# pixelpal.net
KiCad netlist of a schematic drawn in EasyEDA
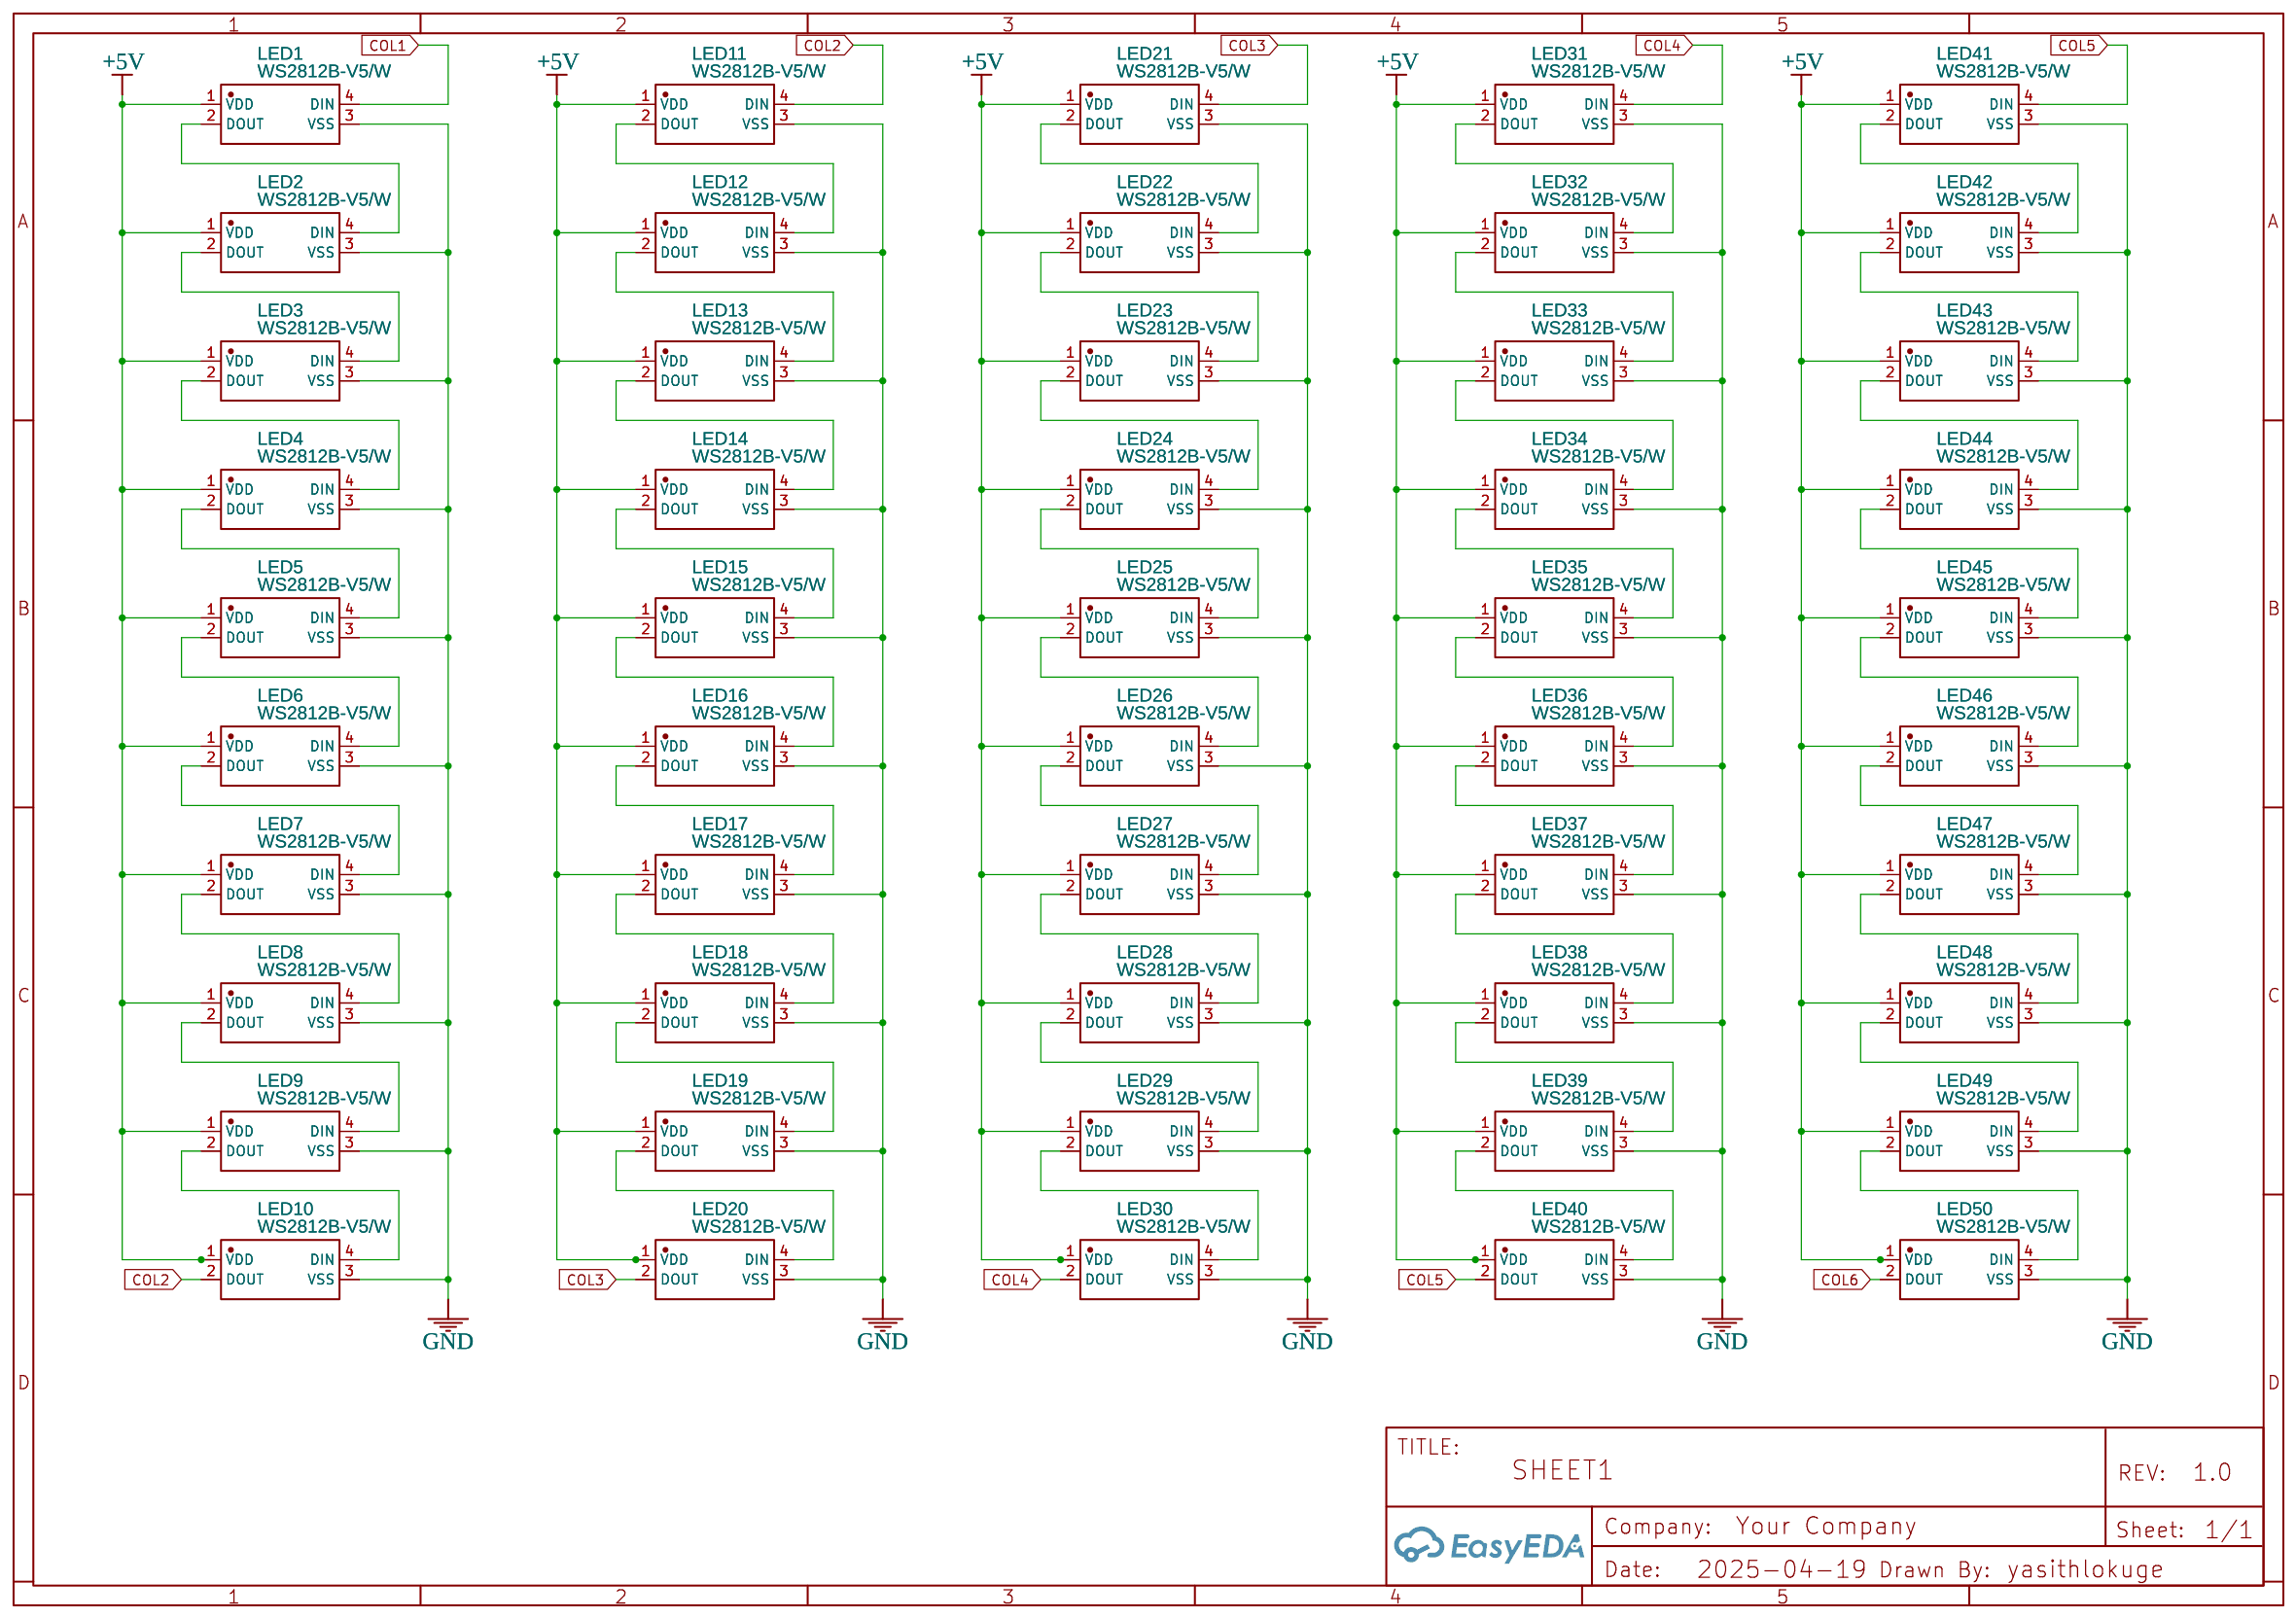
[diagram p0: SHEET1]
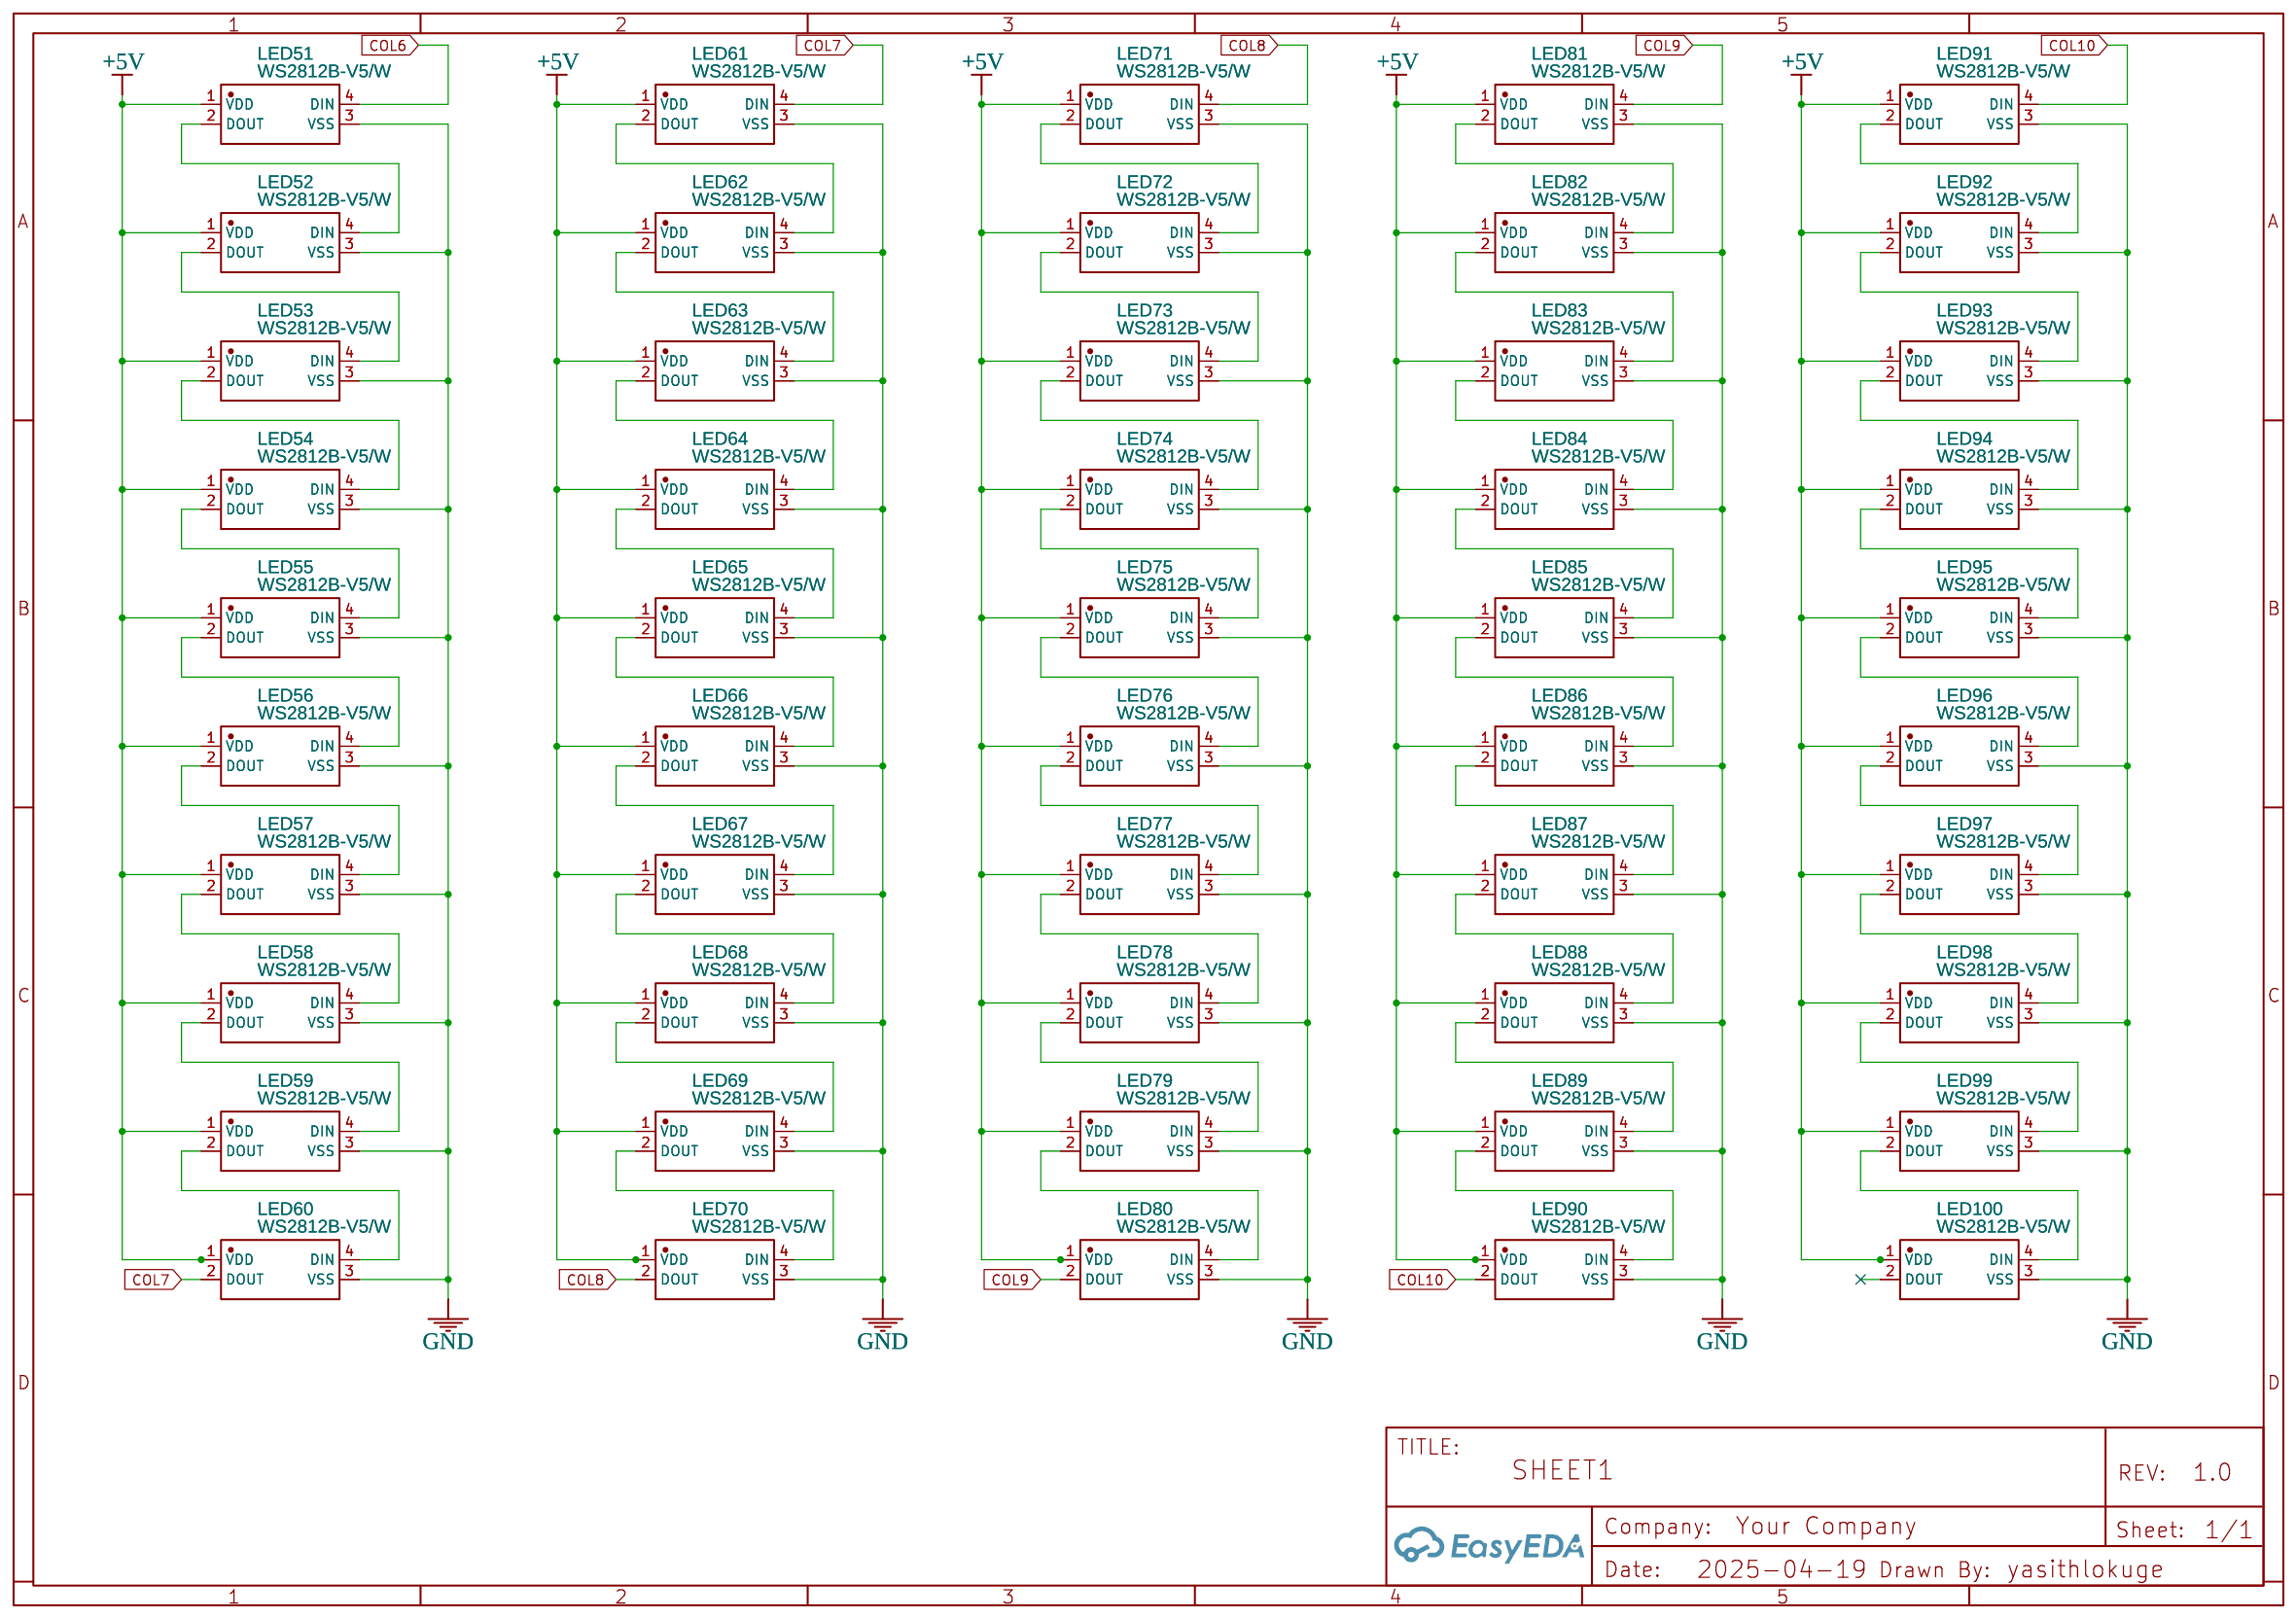
[diagram p1: SHEET2]
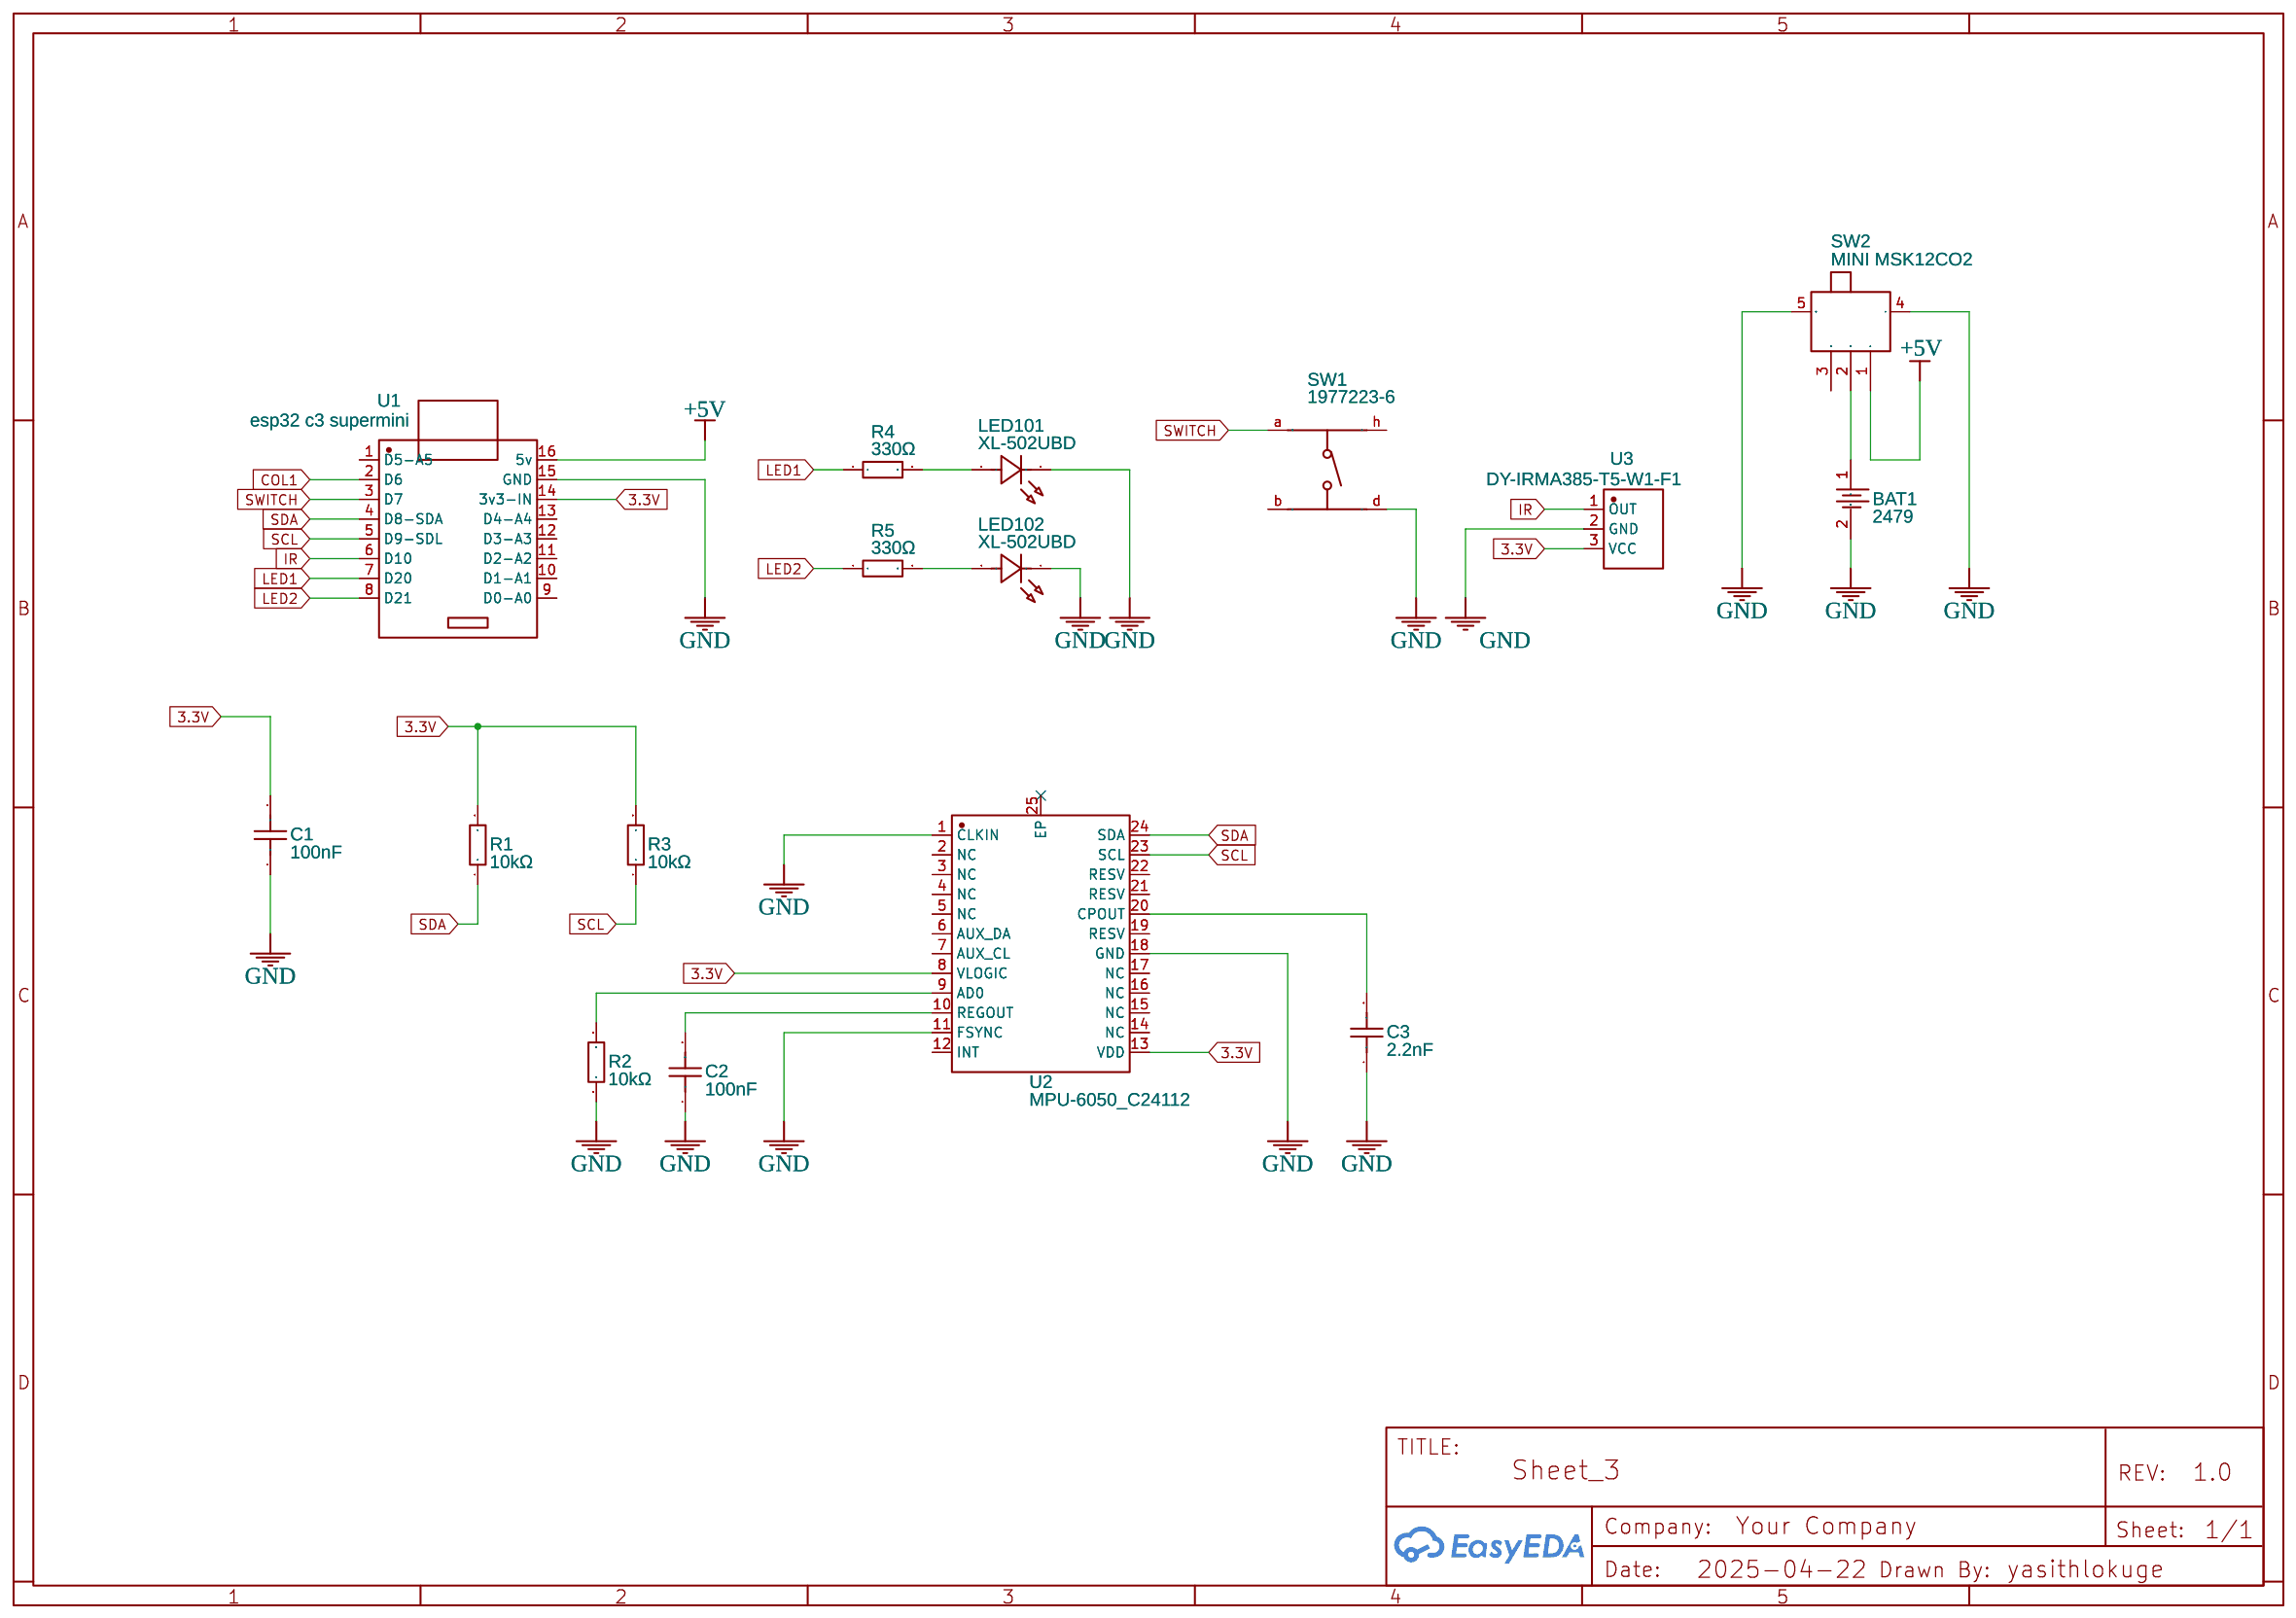
[diagram p2: SHEET3]

(export (version "E")
  (design (tool "Eeschema 10.0.6"))
  (components
    (comp (ref "LED1")
      (value "WS2812B-V5/W")
      (fields (field (name "Manufacturer") "worldsemi"))
      (libsource (lib "") (part "WS2812B-V5/W"))
    )
    (comp (ref "LED2")
      (value "WS2812B-V5/W")
      (fields (field (name "Manufacturer") "worldsemi"))
      (libsource (lib "") (part "WS2812B-V5/W"))
    )
    (comp (ref "LED3")
      (value "WS2812B-V5/W")
      (fields (field (name "Manufacturer") "worldsemi"))
      (libsource (lib "") (part "WS2812B-V5/W"))
    )
    (comp (ref "LED4")
      (value "WS2812B-V5/W")
      (fields (field (name "Manufacturer") "worldsemi"))
      (libsource (lib "") (part "WS2812B-V5/W"))
    )
    (comp (ref "LED5")
      (value "WS2812B-V5/W")
      (fields (field (name "Manufacturer") "worldsemi"))
      (libsource (lib "") (part "WS2812B-V5/W"))
    )
    (comp (ref "LED6")
      (value "WS2812B-V5/W")
      (fields (field (name "Manufacturer") "worldsemi"))
      (libsource (lib "") (part "WS2812B-V5/W"))
    )
    (comp (ref "LED7")
      (value "WS2812B-V5/W")
      (fields (field (name "Manufacturer") "worldsemi"))
      (libsource (lib "") (part "WS2812B-V5/W"))
    )
    (comp (ref "LED8")
      (value "WS2812B-V5/W")
      (fields (field (name "Manufacturer") "worldsemi"))
      (libsource (lib "") (part "WS2812B-V5/W"))
    )
    (comp (ref "LED9")
      (value "WS2812B-V5/W")
      (fields (field (name "Manufacturer") "worldsemi"))
      (libsource (lib "") (part "WS2812B-V5/W"))
    )
    (comp (ref "LED10")
      (value "WS2812B-V5/W")
      (fields (field (name "Manufacturer") "worldsemi"))
      (libsource (lib "") (part "WS2812B-V5/W"))
    )
    (comp (ref "LED11")
      (value "WS2812B-V5/W")
      (fields (field (name "Manufacturer") "worldsemi"))
      (libsource (lib "") (part "WS2812B-V5/W"))
    )
    (comp (ref "LED12")
      (value "WS2812B-V5/W")
      (fields (field (name "Manufacturer") "worldsemi"))
      (libsource (lib "") (part "WS2812B-V5/W"))
    )
    (comp (ref "LED13")
      (value "WS2812B-V5/W")
      (fields (field (name "Manufacturer") "worldsemi"))
      (libsource (lib "") (part "WS2812B-V5/W"))
    )
    (comp (ref "LED14")
      (value "WS2812B-V5/W")
      (fields (field (name "Manufacturer") "worldsemi"))
      (libsource (lib "") (part "WS2812B-V5/W"))
    )
    (comp (ref "LED15")
      (value "WS2812B-V5/W")
      (fields (field (name "Manufacturer") "worldsemi"))
      (libsource (lib "") (part "WS2812B-V5/W"))
    )
    (comp (ref "LED16")
      (value "WS2812B-V5/W")
      (fields (field (name "Manufacturer") "worldsemi"))
      (libsource (lib "") (part "WS2812B-V5/W"))
    )
    (comp (ref "LED17")
      (value "WS2812B-V5/W")
      (fields (field (name "Manufacturer") "worldsemi"))
      (libsource (lib "") (part "WS2812B-V5/W"))
    )
    (comp (ref "LED18")
      (value "WS2812B-V5/W")
      (fields (field (name "Manufacturer") "worldsemi"))
      (libsource (lib "") (part "WS2812B-V5/W"))
    )
    (comp (ref "LED19")
      (value "WS2812B-V5/W")
      (fields (field (name "Manufacturer") "worldsemi"))
      (libsource (lib "") (part "WS2812B-V5/W"))
    )
    (comp (ref "LED20")
      (value "WS2812B-V5/W")
      (fields (field (name "Manufacturer") "worldsemi"))
      (libsource (lib "") (part "WS2812B-V5/W"))
    )
    (comp (ref "LED21")
      (value "WS2812B-V5/W")
      (fields (field (name "Manufacturer") "worldsemi"))
      (libsource (lib "") (part "WS2812B-V5/W"))
    )
    (comp (ref "LED22")
      (value "WS2812B-V5/W")
      (fields (field (name "Manufacturer") "worldsemi"))
      (libsource (lib "") (part "WS2812B-V5/W"))
    )
    (comp (ref "LED23")
      (value "WS2812B-V5/W")
      (fields (field (name "Manufacturer") "worldsemi"))
      (libsource (lib "") (part "WS2812B-V5/W"))
    )
    (comp (ref "LED24")
      (value "WS2812B-V5/W")
      (fields (field (name "Manufacturer") "worldsemi"))
      (libsource (lib "") (part "WS2812B-V5/W"))
    )
    (comp (ref "LED25")
      (value "WS2812B-V5/W")
      (fields (field (name "Manufacturer") "worldsemi"))
      (libsource (lib "") (part "WS2812B-V5/W"))
    )
    (comp (ref "LED26")
      (value "WS2812B-V5/W")
      (fields (field (name "Manufacturer") "worldsemi"))
      (libsource (lib "") (part "WS2812B-V5/W"))
    )
    (comp (ref "LED27")
      (value "WS2812B-V5/W")
      (fields (field (name "Manufacturer") "worldsemi"))
      (libsource (lib "") (part "WS2812B-V5/W"))
    )
    (comp (ref "LED28")
      (value "WS2812B-V5/W")
      (fields (field (name "Manufacturer") "worldsemi"))
      (libsource (lib "") (part "WS2812B-V5/W"))
    )
    (comp (ref "LED29")
      (value "WS2812B-V5/W")
      (fields (field (name "Manufacturer") "worldsemi"))
      (libsource (lib "") (part "WS2812B-V5/W"))
    )
    (comp (ref "LED30")
      (value "WS2812B-V5/W")
      (fields (field (name "Manufacturer") "worldsemi"))
      (libsource (lib "") (part "WS2812B-V5/W"))
    )
    (comp (ref "LED31")
      (value "WS2812B-V5/W")
      (fields (field (name "Manufacturer") "worldsemi"))
      (libsource (lib "") (part "WS2812B-V5/W"))
    )
    (comp (ref "LED32")
      (value "WS2812B-V5/W")
      (fields (field (name "Manufacturer") "worldsemi"))
      (libsource (lib "") (part "WS2812B-V5/W"))
    )
    (comp (ref "LED33")
      (value "WS2812B-V5/W")
      (fields (field (name "Manufacturer") "worldsemi"))
      (libsource (lib "") (part "WS2812B-V5/W"))
    )
    (comp (ref "LED34")
      (value "WS2812B-V5/W")
      (fields (field (name "Manufacturer") "worldsemi"))
      (libsource (lib "") (part "WS2812B-V5/W"))
    )
    (comp (ref "LED35")
      (value "WS2812B-V5/W")
      (fields (field (name "Manufacturer") "worldsemi"))
      (libsource (lib "") (part "WS2812B-V5/W"))
    )
    (comp (ref "LED36")
      (value "WS2812B-V5/W")
      (fields (field (name "Manufacturer") "worldsemi"))
      (libsource (lib "") (part "WS2812B-V5/W"))
    )
    (comp (ref "LED37")
      (value "WS2812B-V5/W")
      (fields (field (name "Manufacturer") "worldsemi"))
      (libsource (lib "") (part "WS2812B-V5/W"))
    )
    (comp (ref "LED38")
      (value "WS2812B-V5/W")
      (fields (field (name "Manufacturer") "worldsemi"))
      (libsource (lib "") (part "WS2812B-V5/W"))
    )
    (comp (ref "LED39")
      (value "WS2812B-V5/W")
      (fields (field (name "Manufacturer") "worldsemi"))
      (libsource (lib "") (part "WS2812B-V5/W"))
    )
    (comp (ref "LED40")
      (value "WS2812B-V5/W")
      (fields (field (name "Manufacturer") "worldsemi"))
      (libsource (lib "") (part "WS2812B-V5/W"))
    )
    (comp (ref "LED41")
      (value "WS2812B-V5/W")
      (fields (field (name "Manufacturer") "worldsemi"))
      (libsource (lib "") (part "WS2812B-V5/W"))
    )
    (comp (ref "LED42")
      (value "WS2812B-V5/W")
      (fields (field (name "Manufacturer") "worldsemi"))
      (libsource (lib "") (part "WS2812B-V5/W"))
    )
    (comp (ref "LED43")
      (value "WS2812B-V5/W")
      (fields (field (name "Manufacturer") "worldsemi"))
      (libsource (lib "") (part "WS2812B-V5/W"))
    )
    (comp (ref "LED44")
      (value "WS2812B-V5/W")
      (fields (field (name "Manufacturer") "worldsemi"))
      (libsource (lib "") (part "WS2812B-V5/W"))
    )
    (comp (ref "LED45")
      (value "WS2812B-V5/W")
      (fields (field (name "Manufacturer") "worldsemi"))
      (libsource (lib "") (part "WS2812B-V5/W"))
    )
    (comp (ref "LED46")
      (value "WS2812B-V5/W")
      (fields (field (name "Manufacturer") "worldsemi"))
      (libsource (lib "") (part "WS2812B-V5/W"))
    )
    (comp (ref "LED47")
      (value "WS2812B-V5/W")
      (fields (field (name "Manufacturer") "worldsemi"))
      (libsource (lib "") (part "WS2812B-V5/W"))
    )
    (comp (ref "LED48")
      (value "WS2812B-V5/W")
      (fields (field (name "Manufacturer") "worldsemi"))
      (libsource (lib "") (part "WS2812B-V5/W"))
    )
    (comp (ref "LED49")
      (value "WS2812B-V5/W")
      (fields (field (name "Manufacturer") "worldsemi"))
      (libsource (lib "") (part "WS2812B-V5/W"))
    )
    (comp (ref "LED50")
      (value "WS2812B-V5/W")
      (fields (field (name "Manufacturer") "worldsemi"))
      (libsource (lib "") (part "WS2812B-V5/W"))
    )
    (comp (ref "LED51")
      (value "WS2812B-V5/W")
      (fields (field (name "Manufacturer") "worldsemi"))
      (libsource (lib "") (part "WS2812B-V5/W"))
    )
    (comp (ref "LED52")
      (value "WS2812B-V5/W")
      (fields (field (name "Manufacturer") "worldsemi"))
      (libsource (lib "") (part "WS2812B-V5/W"))
    )
    (comp (ref "LED53")
      (value "WS2812B-V5/W")
      (fields (field (name "Manufacturer") "worldsemi"))
      (libsource (lib "") (part "WS2812B-V5/W"))
    )
    (comp (ref "LED54")
      (value "WS2812B-V5/W")
      (fields (field (name "Manufacturer") "worldsemi"))
      (libsource (lib "") (part "WS2812B-V5/W"))
    )
    (comp (ref "LED55")
      (value "WS2812B-V5/W")
      (fields (field (name "Manufacturer") "worldsemi"))
      (libsource (lib "") (part "WS2812B-V5/W"))
    )
    (comp (ref "LED56")
      (value "WS2812B-V5/W")
      (fields (field (name "Manufacturer") "worldsemi"))
      (libsource (lib "") (part "WS2812B-V5/W"))
    )
    (comp (ref "LED57")
      (value "WS2812B-V5/W")
      (fields (field (name "Manufacturer") "worldsemi"))
      (libsource (lib "") (part "WS2812B-V5/W"))
    )
    (comp (ref "LED58")
      (value "WS2812B-V5/W")
      (fields (field (name "Manufacturer") "worldsemi"))
      (libsource (lib "") (part "WS2812B-V5/W"))
    )
    (comp (ref "LED59")
      (value "WS2812B-V5/W")
      (fields (field (name "Manufacturer") "worldsemi"))
      (libsource (lib "") (part "WS2812B-V5/W"))
    )
    (comp (ref "LED60")
      (value "WS2812B-V5/W")
      (fields (field (name "Manufacturer") "worldsemi"))
      (libsource (lib "") (part "WS2812B-V5/W"))
    )
    (comp (ref "LED61")
      (value "WS2812B-V5/W")
      (fields (field (name "Manufacturer") "worldsemi"))
      (libsource (lib "") (part "WS2812B-V5/W"))
    )
    (comp (ref "LED62")
      (value "WS2812B-V5/W")
      (fields (field (name "Manufacturer") "worldsemi"))
      (libsource (lib "") (part "WS2812B-V5/W"))
    )
    (comp (ref "LED63")
      (value "WS2812B-V5/W")
      (fields (field (name "Manufacturer") "worldsemi"))
      (libsource (lib "") (part "WS2812B-V5/W"))
    )
    (comp (ref "LED64")
      (value "WS2812B-V5/W")
      (fields (field (name "Manufacturer") "worldsemi"))
      (libsource (lib "") (part "WS2812B-V5/W"))
    )
    (comp (ref "LED65")
      (value "WS2812B-V5/W")
      (fields (field (name "Manufacturer") "worldsemi"))
      (libsource (lib "") (part "WS2812B-V5/W"))
    )
    (comp (ref "LED66")
      (value "WS2812B-V5/W")
      (fields (field (name "Manufacturer") "worldsemi"))
      (libsource (lib "") (part "WS2812B-V5/W"))
    )
    (comp (ref "LED67")
      (value "WS2812B-V5/W")
      (fields (field (name "Manufacturer") "worldsemi"))
      (libsource (lib "") (part "WS2812B-V5/W"))
    )
    (comp (ref "LED68")
      (value "WS2812B-V5/W")
      (fields (field (name "Manufacturer") "worldsemi"))
      (libsource (lib "") (part "WS2812B-V5/W"))
    )
    (comp (ref "LED69")
      (value "WS2812B-V5/W")
      (fields (field (name "Manufacturer") "worldsemi"))
      (libsource (lib "") (part "WS2812B-V5/W"))
    )
    (comp (ref "LED70")
      (value "WS2812B-V5/W")
      (fields (field (name "Manufacturer") "worldsemi"))
      (libsource (lib "") (part "WS2812B-V5/W"))
    )
    (comp (ref "LED71")
      (value "WS2812B-V5/W")
      (fields (field (name "Manufacturer") "worldsemi"))
      (libsource (lib "") (part "WS2812B-V5/W"))
    )
    (comp (ref "LED72")
      (value "WS2812B-V5/W")
      (fields (field (name "Manufacturer") "worldsemi"))
      (libsource (lib "") (part "WS2812B-V5/W"))
    )
    (comp (ref "LED73")
      (value "WS2812B-V5/W")
      (fields (field (name "Manufacturer") "worldsemi"))
      (libsource (lib "") (part "WS2812B-V5/W"))
    )
    (comp (ref "LED74")
      (value "WS2812B-V5/W")
      (fields (field (name "Manufacturer") "worldsemi"))
      (libsource (lib "") (part "WS2812B-V5/W"))
    )
    (comp (ref "LED75")
      (value "WS2812B-V5/W")
      (fields (field (name "Manufacturer") "worldsemi"))
      (libsource (lib "") (part "WS2812B-V5/W"))
    )
    (comp (ref "LED76")
      (value "WS2812B-V5/W")
      (fields (field (name "Manufacturer") "worldsemi"))
      (libsource (lib "") (part "WS2812B-V5/W"))
    )
    (comp (ref "LED77")
      (value "WS2812B-V5/W")
      (fields (field (name "Manufacturer") "worldsemi"))
      (libsource (lib "") (part "WS2812B-V5/W"))
    )
    (comp (ref "LED78")
      (value "WS2812B-V5/W")
      (fields (field (name "Manufacturer") "worldsemi"))
      (libsource (lib "") (part "WS2812B-V5/W"))
    )
    (comp (ref "LED79")
      (value "WS2812B-V5/W")
      (fields (field (name "Manufacturer") "worldsemi"))
      (libsource (lib "") (part "WS2812B-V5/W"))
    )
    (comp (ref "LED80")
      (value "WS2812B-V5/W")
      (fields (field (name "Manufacturer") "worldsemi"))
      (libsource (lib "") (part "WS2812B-V5/W"))
    )
    (comp (ref "LED81")
      (value "WS2812B-V5/W")
      (fields (field (name "Manufacturer") "worldsemi"))
      (libsource (lib "") (part "WS2812B-V5/W"))
    )
    (comp (ref "LED82")
      (value "WS2812B-V5/W")
      (fields (field (name "Manufacturer") "worldsemi"))
      (libsource (lib "") (part "WS2812B-V5/W"))
    )
    (comp (ref "LED83")
      (value "WS2812B-V5/W")
      (fields (field (name "Manufacturer") "worldsemi"))
      (libsource (lib "") (part "WS2812B-V5/W"))
    )
    (comp (ref "LED84")
      (value "WS2812B-V5/W")
      (fields (field (name "Manufacturer") "worldsemi"))
      (libsource (lib "") (part "WS2812B-V5/W"))
    )
    (comp (ref "LED85")
      (value "WS2812B-V5/W")
      (fields (field (name "Manufacturer") "worldsemi"))
      (libsource (lib "") (part "WS2812B-V5/W"))
    )
    (comp (ref "LED86")
      (value "WS2812B-V5/W")
      (fields (field (name "Manufacturer") "worldsemi"))
      (libsource (lib "") (part "WS2812B-V5/W"))
    )
    (comp (ref "LED87")
      (value "WS2812B-V5/W")
      (fields (field (name "Manufacturer") "worldsemi"))
      (libsource (lib "") (part "WS2812B-V5/W"))
    )
    (comp (ref "LED88")
      (value "WS2812B-V5/W")
      (fields (field (name "Manufacturer") "worldsemi"))
      (libsource (lib "") (part "WS2812B-V5/W"))
    )
    (comp (ref "LED89")
      (value "WS2812B-V5/W")
      (fields (field (name "Manufacturer") "worldsemi"))
      (libsource (lib "") (part "WS2812B-V5/W"))
    )
    (comp (ref "LED90")
      (value "WS2812B-V5/W")
      (fields (field (name "Manufacturer") "worldsemi"))
      (libsource (lib "") (part "WS2812B-V5/W"))
    )
    (comp (ref "LED91")
      (value "WS2812B-V5/W")
      (fields (field (name "Manufacturer") "worldsemi"))
      (libsource (lib "") (part "WS2812B-V5/W"))
    )
    (comp (ref "LED92")
      (value "WS2812B-V5/W")
      (fields (field (name "Manufacturer") "worldsemi"))
      (libsource (lib "") (part "WS2812B-V5/W"))
    )
    (comp (ref "LED93")
      (value "WS2812B-V5/W")
      (fields (field (name "Manufacturer") "worldsemi"))
      (libsource (lib "") (part "WS2812B-V5/W"))
    )
    (comp (ref "LED94")
      (value "WS2812B-V5/W")
      (fields (field (name "Manufacturer") "worldsemi"))
      (libsource (lib "") (part "WS2812B-V5/W"))
    )
    (comp (ref "LED95")
      (value "WS2812B-V5/W")
      (fields (field (name "Manufacturer") "worldsemi"))
      (libsource (lib "") (part "WS2812B-V5/W"))
    )
    (comp (ref "LED96")
      (value "WS2812B-V5/W")
      (fields (field (name "Manufacturer") "worldsemi"))
      (libsource (lib "") (part "WS2812B-V5/W"))
    )
    (comp (ref "LED97")
      (value "WS2812B-V5/W")
      (fields (field (name "Manufacturer") "worldsemi"))
      (libsource (lib "") (part "WS2812B-V5/W"))
    )
    (comp (ref "LED98")
      (value "WS2812B-V5/W")
      (fields (field (name "Manufacturer") "worldsemi"))
      (libsource (lib "") (part "WS2812B-V5/W"))
    )
    (comp (ref "LED99")
      (value "WS2812B-V5/W")
      (fields (field (name "Manufacturer") "worldsemi"))
      (libsource (lib "") (part "WS2812B-V5/W"))
    )
    (comp (ref "LED100")
      (value "WS2812B-V5/W")
      (fields (field (name "Manufacturer") "worldsemi"))
      (libsource (lib "") (part "WS2812B-V5/W"))
    )
    (comp (ref "BAT1")
      (value "2479")
      (fields (field (name "Manufacturer") "Keystone"))
      (libsource (lib "") (part "2479"))
    )
    (comp (ref "C1")
      (value "100nF")
      (fields
        (field (name "Manufacturer Part") "CL05B104KP5VPNC")
        (field (name "Manufacturer") "SAMSUNG(三星)")
      )
      (libsource (lib "") (part "CL05B104KP5VPNC"))
    )
    (comp (ref "C2")
      (value "100nF")
      (fields
        (field (name "Manufacturer Part") "CL05B104KP5VPNC")
        (field (name "Manufacturer") "SAMSUNG(三星)")
      )
      (libsource (lib "") (part "CL05B104KP5VPNC"))
    )
    (comp (ref "C3")
      (value "2.2nF")
      (fields
        (field (name "Manufacturer Part") "GRM1555C1H222GA01D")
        (field (name "Manufacturer") "muRata(村田)")
      )
      (libsource (lib "") (part "GRM1555C1H222GA01D"))
    )
    (comp (ref "LED101")
      (value "XL-502UBD")
      (fields (field (name "Manufacturer") "XINGLIGHT(成兴光)"))
      (libsource (lib "") (part "XL-502UBD"))
    )
    (comp (ref "LED102")
      (value "XL-502UBD")
      (fields (field (name "Manufacturer") "XINGLIGHT(成兴光)"))
      (libsource (lib "") (part "XL-502UBD"))
    )
    (comp (ref "R1")
      (value "10kΩ")
      (fields (field (name "Manufacturer Part") "ERJ3RBD1002V") (field (name "Manufacturer") "PANASONIC(松下)"))
      (libsource (lib "") (part "ERJ3RBD1002V"))
    )
    (comp (ref "R2")
      (value "10kΩ")
      (fields (field (name "Manufacturer Part") "ERJ3RBD1002V") (field (name "Manufacturer") "PANASONIC(松下)"))
      (libsource (lib "") (part "ERJ3RBD1002V"))
    )
    (comp (ref "R3")
      (value "10kΩ")
      (fields (field (name "Manufacturer Part") "ERJ3RBD1002V") (field (name "Manufacturer") "PANASONIC(松下)"))
      (libsource (lib "") (part "ERJ3RBD1002V"))
    )
    (comp (ref "R4")
      (value "330Ω")
      (fields (field (name "Manufacturer Part") "RS-03K331JT") (field (name "Manufacturer") "FH(风华)"))
      (libsource (lib "") (part "330R 5% 0603"))
    )
    (comp (ref "R5")
      (value "330Ω")
      (fields (field (name "Manufacturer Part") "RS-03K331JT") (field (name "Manufacturer") "FH(风华)"))
      (libsource (lib "") (part "330R 5% 0603"))
    )
    (comp (ref "SW1")
      (value "1977223-6")
      (fields (field (name "Manufacturer") "TE Connectivity(泰科电子)"))
      (libsource (lib "") (part "1977223-6"))
    )
    (comp (ref "SW2")
      (value "MINI MSK12CO2")
      (fields (field (name "Manufacturer") "SHOU HAN(首韩)"))
      (libsource (lib "") (part "MINI MSK12CO2"))
    )
    (comp (ref "U1")
      (value "esp32 c3 supermini")
      (fields
        (field (name "Manufacturer Part") "WT8266-S6 ESP-12S")
        (field (name "Manufacturer") "Wireless-tag(启明云端)")
      )
      (libsource (lib "") (part "esp32 c3 supermini"))
    )
    (comp (ref "U2")
      (value "MPU-6050_C24112")
      (fields
        (field (name "Manufacturer Part") "MPU-6050")
        (field (name "Manufacturer") "TDK InvenSense(应美盛)")
      )
      (libsource (lib "") (part "MPU-6050_C24112"))
    )
    (comp (ref "U3")
      (value "DY-IRMA385-T5-W1-F1")
      (fields (field (name "Manufacturer") "TONYU(东裕)"))
      (libsource (lib "") (part "DY-IRMA385-T5-W1-F1"))
    )
  )
  (nets
    (net (code "1") (name "+5V") (class "Default")
      (node (ref "LED1") (pin "1") (pinfunction "VDD_1") (pintype "unspecified"))
      (node (ref "LED10") (pin "1") (pinfunction "VDD_1") (pintype "unspecified"))
      (node (ref "LED100") (pin "1") (pinfunction "VDD_1") (pintype "unspecified"))
      (node (ref "LED11") (pin "1") (pinfunction "VDD_1") (pintype "unspecified"))
      (node (ref "LED12") (pin "1") (pinfunction "VDD_1") (pintype "unspecified"))
      (node (ref "LED13") (pin "1") (pinfunction "VDD_1") (pintype "unspecified"))
      (node (ref "LED14") (pin "1") (pinfunction "VDD_1") (pintype "unspecified"))
      (node (ref "LED15") (pin "1") (pinfunction "VDD_1") (pintype "unspecified"))
      (node (ref "LED16") (pin "1") (pinfunction "VDD_1") (pintype "unspecified"))
      (node (ref "LED17") (pin "1") (pinfunction "VDD_1") (pintype "unspecified"))
      (node (ref "LED18") (pin "1") (pinfunction "VDD_1") (pintype "unspecified"))
      (node (ref "LED19") (pin "1") (pinfunction "VDD_1") (pintype "unspecified"))
      (node (ref "LED2") (pin "1") (pinfunction "VDD_1") (pintype "unspecified"))
      (node (ref "LED20") (pin "1") (pinfunction "VDD_1") (pintype "unspecified"))
      (node (ref "LED21") (pin "1") (pinfunction "VDD_1") (pintype "unspecified"))
      (node (ref "LED22") (pin "1") (pinfunction "VDD_1") (pintype "unspecified"))
      (node (ref "LED23") (pin "1") (pinfunction "VDD_1") (pintype "unspecified"))
      (node (ref "LED24") (pin "1") (pinfunction "VDD_1") (pintype "unspecified"))
      (node (ref "LED25") (pin "1") (pinfunction "VDD_1") (pintype "unspecified"))
      (node (ref "LED26") (pin "1") (pinfunction "VDD_1") (pintype "unspecified"))
      (node (ref "LED27") (pin "1") (pinfunction "VDD_1") (pintype "unspecified"))
      (node (ref "LED28") (pin "1") (pinfunction "VDD_1") (pintype "unspecified"))
      (node (ref "LED29") (pin "1") (pinfunction "VDD_1") (pintype "unspecified"))
      (node (ref "LED3") (pin "1") (pinfunction "VDD_1") (pintype "unspecified"))
      (node (ref "LED30") (pin "1") (pinfunction "VDD_1") (pintype "unspecified"))
      (node (ref "LED31") (pin "1") (pinfunction "VDD_1") (pintype "unspecified"))
      (node (ref "LED32") (pin "1") (pinfunction "VDD_1") (pintype "unspecified"))
      (node (ref "LED33") (pin "1") (pinfunction "VDD_1") (pintype "unspecified"))
      (node (ref "LED34") (pin "1") (pinfunction "VDD_1") (pintype "unspecified"))
      (node (ref "LED35") (pin "1") (pinfunction "VDD_1") (pintype "unspecified"))
      (node (ref "LED36") (pin "1") (pinfunction "VDD_1") (pintype "unspecified"))
      (node (ref "LED37") (pin "1") (pinfunction "VDD_1") (pintype "unspecified"))
      (node (ref "LED38") (pin "1") (pinfunction "VDD_1") (pintype "unspecified"))
      (node (ref "LED39") (pin "1") (pinfunction "VDD_1") (pintype "unspecified"))
      (node (ref "LED4") (pin "1") (pinfunction "VDD_1") (pintype "unspecified"))
      (node (ref "LED40") (pin "1") (pinfunction "VDD_1") (pintype "unspecified"))
      (node (ref "LED41") (pin "1") (pinfunction "VDD_1") (pintype "unspecified"))
      (node (ref "LED42") (pin "1") (pinfunction "VDD_1") (pintype "unspecified"))
      (node (ref "LED43") (pin "1") (pinfunction "VDD_1") (pintype "unspecified"))
      (node (ref "LED44") (pin "1") (pinfunction "VDD_1") (pintype "unspecified"))
      (node (ref "LED45") (pin "1") (pinfunction "VDD_1") (pintype "unspecified"))
      (node (ref "LED46") (pin "1") (pinfunction "VDD_1") (pintype "unspecified"))
      (node (ref "LED47") (pin "1") (pinfunction "VDD_1") (pintype "unspecified"))
      (node (ref "LED48") (pin "1") (pinfunction "VDD_1") (pintype "unspecified"))
      (node (ref "LED49") (pin "1") (pinfunction "VDD_1") (pintype "unspecified"))
      (node (ref "LED5") (pin "1") (pinfunction "VDD_1") (pintype "unspecified"))
      (node (ref "LED50") (pin "1") (pinfunction "VDD_1") (pintype "unspecified"))
      (node (ref "LED51") (pin "1") (pinfunction "VDD_1") (pintype "unspecified"))
      (node (ref "LED52") (pin "1") (pinfunction "VDD_1") (pintype "unspecified"))
      (node (ref "LED53") (pin "1") (pinfunction "VDD_1") (pintype "unspecified"))
      (node (ref "LED54") (pin "1") (pinfunction "VDD_1") (pintype "unspecified"))
      (node (ref "LED55") (pin "1") (pinfunction "VDD_1") (pintype "unspecified"))
      (node (ref "LED56") (pin "1") (pinfunction "VDD_1") (pintype "unspecified"))
      (node (ref "LED57") (pin "1") (pinfunction "VDD_1") (pintype "unspecified"))
      (node (ref "LED58") (pin "1") (pinfunction "VDD_1") (pintype "unspecified"))
      (node (ref "LED59") (pin "1") (pinfunction "VDD_1") (pintype "unspecified"))
      (node (ref "LED6") (pin "1") (pinfunction "VDD_1") (pintype "unspecified"))
      (node (ref "LED60") (pin "1") (pinfunction "VDD_1") (pintype "unspecified"))
      (node (ref "LED61") (pin "1") (pinfunction "VDD_1") (pintype "unspecified"))
      (node (ref "LED62") (pin "1") (pinfunction "VDD_1") (pintype "unspecified"))
      (node (ref "LED63") (pin "1") (pinfunction "VDD_1") (pintype "unspecified"))
      (node (ref "LED64") (pin "1") (pinfunction "VDD_1") (pintype "unspecified"))
      (node (ref "LED65") (pin "1") (pinfunction "VDD_1") (pintype "unspecified"))
      (node (ref "LED66") (pin "1") (pinfunction "VDD_1") (pintype "unspecified"))
      (node (ref "LED67") (pin "1") (pinfunction "VDD_1") (pintype "unspecified"))
      (node (ref "LED68") (pin "1") (pinfunction "VDD_1") (pintype "unspecified"))
      (node (ref "LED69") (pin "1") (pinfunction "VDD_1") (pintype "unspecified"))
      (node (ref "LED7") (pin "1") (pinfunction "VDD_1") (pintype "unspecified"))
      (node (ref "LED70") (pin "1") (pinfunction "VDD_1") (pintype "unspecified"))
      (node (ref "LED71") (pin "1") (pinfunction "VDD_1") (pintype "unspecified"))
      (node (ref "LED72") (pin "1") (pinfunction "VDD_1") (pintype "unspecified"))
      (node (ref "LED73") (pin "1") (pinfunction "VDD_1") (pintype "unspecified"))
      (node (ref "LED74") (pin "1") (pinfunction "VDD_1") (pintype "unspecified"))
      (node (ref "LED75") (pin "1") (pinfunction "VDD_1") (pintype "unspecified"))
      (node (ref "LED76") (pin "1") (pinfunction "VDD_1") (pintype "unspecified"))
      (node (ref "LED77") (pin "1") (pinfunction "VDD_1") (pintype "unspecified"))
      (node (ref "LED78") (pin "1") (pinfunction "VDD_1") (pintype "unspecified"))
      (node (ref "LED79") (pin "1") (pinfunction "VDD_1") (pintype "unspecified"))
      (node (ref "LED8") (pin "1") (pinfunction "VDD_1") (pintype "unspecified"))
      (node (ref "LED80") (pin "1") (pinfunction "VDD_1") (pintype "unspecified"))
      (node (ref "LED81") (pin "1") (pinfunction "VDD_1") (pintype "unspecified"))
      (node (ref "LED82") (pin "1") (pinfunction "VDD_1") (pintype "unspecified"))
      (node (ref "LED83") (pin "1") (pinfunction "VDD_1") (pintype "unspecified"))
      (node (ref "LED84") (pin "1") (pinfunction "VDD_1") (pintype "unspecified"))
      (node (ref "LED85") (pin "1") (pinfunction "VDD_1") (pintype "unspecified"))
      (node (ref "LED86") (pin "1") (pinfunction "VDD_1") (pintype "unspecified"))
      (node (ref "LED87") (pin "1") (pinfunction "VDD_1") (pintype "unspecified"))
      (node (ref "LED88") (pin "1") (pinfunction "VDD_1") (pintype "unspecified"))
      (node (ref "LED89") (pin "1") (pinfunction "VDD_1") (pintype "unspecified"))
      (node (ref "LED9") (pin "1") (pinfunction "VDD_1") (pintype "unspecified"))
      (node (ref "LED90") (pin "1") (pinfunction "VDD_1") (pintype "unspecified"))
      (node (ref "LED91") (pin "1") (pinfunction "VDD_1") (pintype "unspecified"))
      (node (ref "LED92") (pin "1") (pinfunction "VDD_1") (pintype "unspecified"))
      (node (ref "LED93") (pin "1") (pinfunction "VDD_1") (pintype "unspecified"))
      (node (ref "LED94") (pin "1") (pinfunction "VDD_1") (pintype "unspecified"))
      (node (ref "LED95") (pin "1") (pinfunction "VDD_1") (pintype "unspecified"))
      (node (ref "LED96") (pin "1") (pinfunction "VDD_1") (pintype "unspecified"))
      (node (ref "LED97") (pin "1") (pinfunction "VDD_1") (pintype "unspecified"))
      (node (ref "LED98") (pin "1") (pinfunction "VDD_1") (pintype "unspecified"))
      (node (ref "LED99") (pin "1") (pinfunction "VDD_1") (pintype "unspecified"))
      (node (ref "SW2") (pin "1") (pinfunction "1_1") (pintype "unspecified"))
      (node (ref "U1") (pin "16") (pinfunction "5v_16") (pintype "unspecified"))
    )
    (net (code "2") (name "3.3V") (class "Default")
      (node (ref "C1") (pin "2") (pinfunction "2_2") (pintype "unspecified"))
      (node (ref "R1") (pin "2") (pinfunction "2_2") (pintype "unspecified"))
      (node (ref "R3") (pin "2") (pinfunction "2_2") (pintype "unspecified"))
      (node (ref "U1") (pin "14") (pinfunction "3v3-IN_14") (pintype "unspecified"))
      (node (ref "U2") (pin "13") (pinfunction "VDD_13") (pintype "unspecified"))
      (node (ref "U2") (pin "8") (pinfunction "VLOGIC_8") (pintype "unspecified"))
      (node (ref "U3") (pin "3") (pinfunction "VCC_3") (pintype "unspecified"))
    )
    (net (code "3") (name "COL1") (class "Default")
      (node (ref "LED1") (pin "4") (pinfunction "DIN_4") (pintype "unspecified"))
      (node (ref "U1") (pin "2") (pinfunction "D6_2") (pintype "unspecified"))
    )
    (net (code "4") (name "COL2") (class "Default")
      (node (ref "LED10") (pin "2") (pinfunction "DOUT_2") (pintype "unspecified"))
      (node (ref "LED11") (pin "4") (pinfunction "DIN_4") (pintype "unspecified"))
    )
    (net (code "5") (name "COL3") (class "Default")
      (node (ref "LED20") (pin "2") (pinfunction "DOUT_2") (pintype "unspecified"))
      (node (ref "LED21") (pin "4") (pinfunction "DIN_4") (pintype "unspecified"))
    )
    (net (code "6") (name "COL4") (class "Default")
      (node (ref "LED30") (pin "2") (pinfunction "DOUT_2") (pintype "unspecified"))
      (node (ref "LED31") (pin "4") (pinfunction "DIN_4") (pintype "unspecified"))
    )
    (net (code "7") (name "COL5") (class "Default")
      (node (ref "LED40") (pin "2") (pinfunction "DOUT_2") (pintype "unspecified"))
      (node (ref "LED41") (pin "4") (pinfunction "DIN_4") (pintype "unspecified"))
    )
    (net (code "8") (name "COL6") (class "Default")
      (node (ref "LED50") (pin "2") (pinfunction "DOUT_2") (pintype "unspecified"))
      (node (ref "LED51") (pin "4") (pinfunction "DIN_4") (pintype "unspecified"))
    )
    (net (code "9") (name "COL7") (class "Default")
      (node (ref "LED60") (pin "2") (pinfunction "DOUT_2") (pintype "unspecified"))
      (node (ref "LED61") (pin "4") (pinfunction "DIN_4") (pintype "unspecified"))
    )
    (net (code "10") (name "COL8") (class "Default")
      (node (ref "LED70") (pin "2") (pinfunction "DOUT_2") (pintype "unspecified"))
      (node (ref "LED71") (pin "4") (pinfunction "DIN_4") (pintype "unspecified"))
    )
    (net (code "11") (name "COL9") (class "Default")
      (node (ref "LED80") (pin "2") (pinfunction "DOUT_2") (pintype "unspecified"))
      (node (ref "LED81") (pin "4") (pinfunction "DIN_4") (pintype "unspecified"))
    )
    (net (code "12") (name "COL10") (class "Default")
      (node (ref "LED90") (pin "2") (pinfunction "DOUT_2") (pintype "unspecified"))
      (node (ref "LED91") (pin "4") (pinfunction "DIN_4") (pintype "unspecified"))
    )
    (net (code "13") (name "GND") (class "Default")
      (node (ref "BAT1") (pin "2") (pinfunction "2_2") (pintype "input"))
      (node (ref "C1") (pin "1") (pinfunction "1_1") (pintype "unspecified"))
      (node (ref "C2") (pin "1") (pinfunction "1_1") (pintype "unspecified"))
      (node (ref "C3") (pin "1") (pinfunction "1_1") (pintype "unspecified"))
      (node (ref "LED1") (pin "3") (pinfunction "VSS_3") (pintype "unspecified"))
      (node (ref "LED10") (pin "3") (pinfunction "VSS_3") (pintype "unspecified"))
      (node (ref "LED100") (pin "3") (pinfunction "VSS_3") (pintype "unspecified"))
      (node (ref "LED101") (pin "1") (pinfunction "K_1") (pintype "unspecified"))
      (node (ref "LED102") (pin "1") (pinfunction "K_1") (pintype "unspecified"))
      (node (ref "LED11") (pin "3") (pinfunction "VSS_3") (pintype "unspecified"))
      (node (ref "LED12") (pin "3") (pinfunction "VSS_3") (pintype "unspecified"))
      (node (ref "LED13") (pin "3") (pinfunction "VSS_3") (pintype "unspecified"))
      (node (ref "LED14") (pin "3") (pinfunction "VSS_3") (pintype "unspecified"))
      (node (ref "LED15") (pin "3") (pinfunction "VSS_3") (pintype "unspecified"))
      (node (ref "LED16") (pin "3") (pinfunction "VSS_3") (pintype "unspecified"))
      (node (ref "LED17") (pin "3") (pinfunction "VSS_3") (pintype "unspecified"))
      (node (ref "LED18") (pin "3") (pinfunction "VSS_3") (pintype "unspecified"))
      (node (ref "LED19") (pin "3") (pinfunction "VSS_3") (pintype "unspecified"))
      (node (ref "LED2") (pin "3") (pinfunction "VSS_3") (pintype "unspecified"))
      (node (ref "LED20") (pin "3") (pinfunction "VSS_3") (pintype "unspecified"))
      (node (ref "LED21") (pin "3") (pinfunction "VSS_3") (pintype "unspecified"))
      (node (ref "LED22") (pin "3") (pinfunction "VSS_3") (pintype "unspecified"))
      (node (ref "LED23") (pin "3") (pinfunction "VSS_3") (pintype "unspecified"))
      (node (ref "LED24") (pin "3") (pinfunction "VSS_3") (pintype "unspecified"))
      (node (ref "LED25") (pin "3") (pinfunction "VSS_3") (pintype "unspecified"))
      (node (ref "LED26") (pin "3") (pinfunction "VSS_3") (pintype "unspecified"))
      (node (ref "LED27") (pin "3") (pinfunction "VSS_3") (pintype "unspecified"))
      (node (ref "LED28") (pin "3") (pinfunction "VSS_3") (pintype "unspecified"))
      (node (ref "LED29") (pin "3") (pinfunction "VSS_3") (pintype "unspecified"))
      (node (ref "LED3") (pin "3") (pinfunction "VSS_3") (pintype "unspecified"))
      (node (ref "LED30") (pin "3") (pinfunction "VSS_3") (pintype "unspecified"))
      (node (ref "LED31") (pin "3") (pinfunction "VSS_3") (pintype "unspecified"))
      (node (ref "LED32") (pin "3") (pinfunction "VSS_3") (pintype "unspecified"))
      (node (ref "LED33") (pin "3") (pinfunction "VSS_3") (pintype "unspecified"))
      (node (ref "LED34") (pin "3") (pinfunction "VSS_3") (pintype "unspecified"))
      (node (ref "LED35") (pin "3") (pinfunction "VSS_3") (pintype "unspecified"))
      (node (ref "LED36") (pin "3") (pinfunction "VSS_3") (pintype "unspecified"))
      (node (ref "LED37") (pin "3") (pinfunction "VSS_3") (pintype "unspecified"))
      (node (ref "LED38") (pin "3") (pinfunction "VSS_3") (pintype "unspecified"))
      (node (ref "LED39") (pin "3") (pinfunction "VSS_3") (pintype "unspecified"))
      (node (ref "LED4") (pin "3") (pinfunction "VSS_3") (pintype "unspecified"))
      (node (ref "LED40") (pin "3") (pinfunction "VSS_3") (pintype "unspecified"))
      (node (ref "LED41") (pin "3") (pinfunction "VSS_3") (pintype "unspecified"))
      (node (ref "LED42") (pin "3") (pinfunction "VSS_3") (pintype "unspecified"))
      (node (ref "LED43") (pin "3") (pinfunction "VSS_3") (pintype "unspecified"))
      (node (ref "LED44") (pin "3") (pinfunction "VSS_3") (pintype "unspecified"))
      (node (ref "LED45") (pin "3") (pinfunction "VSS_3") (pintype "unspecified"))
      (node (ref "LED46") (pin "3") (pinfunction "VSS_3") (pintype "unspecified"))
      (node (ref "LED47") (pin "3") (pinfunction "VSS_3") (pintype "unspecified"))
      (node (ref "LED48") (pin "3") (pinfunction "VSS_3") (pintype "unspecified"))
      (node (ref "LED49") (pin "3") (pinfunction "VSS_3") (pintype "unspecified"))
      (node (ref "LED5") (pin "3") (pinfunction "VSS_3") (pintype "unspecified"))
      (node (ref "LED50") (pin "3") (pinfunction "VSS_3") (pintype "unspecified"))
      (node (ref "LED51") (pin "3") (pinfunction "VSS_3") (pintype "unspecified"))
      (node (ref "LED52") (pin "3") (pinfunction "VSS_3") (pintype "unspecified"))
      (node (ref "LED53") (pin "3") (pinfunction "VSS_3") (pintype "unspecified"))
      (node (ref "LED54") (pin "3") (pinfunction "VSS_3") (pintype "unspecified"))
      (node (ref "LED55") (pin "3") (pinfunction "VSS_3") (pintype "unspecified"))
      (node (ref "LED56") (pin "3") (pinfunction "VSS_3") (pintype "unspecified"))
      (node (ref "LED57") (pin "3") (pinfunction "VSS_3") (pintype "unspecified"))
      (node (ref "LED58") (pin "3") (pinfunction "VSS_3") (pintype "unspecified"))
      (node (ref "LED59") (pin "3") (pinfunction "VSS_3") (pintype "unspecified"))
      (node (ref "LED6") (pin "3") (pinfunction "VSS_3") (pintype "unspecified"))
      (node (ref "LED60") (pin "3") (pinfunction "VSS_3") (pintype "unspecified"))
      (node (ref "LED61") (pin "3") (pinfunction "VSS_3") (pintype "unspecified"))
      (node (ref "LED62") (pin "3") (pinfunction "VSS_3") (pintype "unspecified"))
      (node (ref "LED63") (pin "3") (pinfunction "VSS_3") (pintype "unspecified"))
      (node (ref "LED64") (pin "3") (pinfunction "VSS_3") (pintype "unspecified"))
      (node (ref "LED65") (pin "3") (pinfunction "VSS_3") (pintype "unspecified"))
      (node (ref "LED66") (pin "3") (pinfunction "VSS_3") (pintype "unspecified"))
      (node (ref "LED67") (pin "3") (pinfunction "VSS_3") (pintype "unspecified"))
      (node (ref "LED68") (pin "3") (pinfunction "VSS_3") (pintype "unspecified"))
      (node (ref "LED69") (pin "3") (pinfunction "VSS_3") (pintype "unspecified"))
      (node (ref "LED7") (pin "3") (pinfunction "VSS_3") (pintype "unspecified"))
      (node (ref "LED70") (pin "3") (pinfunction "VSS_3") (pintype "unspecified"))
      (node (ref "LED71") (pin "3") (pinfunction "VSS_3") (pintype "unspecified"))
      (node (ref "LED72") (pin "3") (pinfunction "VSS_3") (pintype "unspecified"))
      (node (ref "LED73") (pin "3") (pinfunction "VSS_3") (pintype "unspecified"))
      (node (ref "LED74") (pin "3") (pinfunction "VSS_3") (pintype "unspecified"))
      (node (ref "LED75") (pin "3") (pinfunction "VSS_3") (pintype "unspecified"))
      (node (ref "LED76") (pin "3") (pinfunction "VSS_3") (pintype "unspecified"))
      (node (ref "LED77") (pin "3") (pinfunction "VSS_3") (pintype "unspecified"))
      (node (ref "LED78") (pin "3") (pinfunction "VSS_3") (pintype "unspecified"))
      (node (ref "LED79") (pin "3") (pinfunction "VSS_3") (pintype "unspecified"))
      (node (ref "LED8") (pin "3") (pinfunction "VSS_3") (pintype "unspecified"))
      (node (ref "LED80") (pin "3") (pinfunction "VSS_3") (pintype "unspecified"))
      (node (ref "LED81") (pin "3") (pinfunction "VSS_3") (pintype "unspecified"))
      (node (ref "LED82") (pin "3") (pinfunction "VSS_3") (pintype "unspecified"))
      (node (ref "LED83") (pin "3") (pinfunction "VSS_3") (pintype "unspecified"))
      (node (ref "LED84") (pin "3") (pinfunction "VSS_3") (pintype "unspecified"))
      (node (ref "LED85") (pin "3") (pinfunction "VSS_3") (pintype "unspecified"))
      (node (ref "LED86") (pin "3") (pinfunction "VSS_3") (pintype "unspecified"))
      (node (ref "LED87") (pin "3") (pinfunction "VSS_3") (pintype "unspecified"))
      (node (ref "LED88") (pin "3") (pinfunction "VSS_3") (pintype "unspecified"))
      (node (ref "LED89") (pin "3") (pinfunction "VSS_3") (pintype "unspecified"))
      (node (ref "LED9") (pin "3") (pinfunction "VSS_3") (pintype "unspecified"))
      (node (ref "LED90") (pin "3") (pinfunction "VSS_3") (pintype "unspecified"))
      (node (ref "LED91") (pin "3") (pinfunction "VSS_3") (pintype "unspecified"))
      (node (ref "LED92") (pin "3") (pinfunction "VSS_3") (pintype "unspecified"))
      (node (ref "LED93") (pin "3") (pinfunction "VSS_3") (pintype "unspecified"))
      (node (ref "LED94") (pin "3") (pinfunction "VSS_3") (pintype "unspecified"))
      (node (ref "LED95") (pin "3") (pinfunction "VSS_3") (pintype "unspecified"))
      (node (ref "LED96") (pin "3") (pinfunction "VSS_3") (pintype "unspecified"))
      (node (ref "LED97") (pin "3") (pinfunction "VSS_3") (pintype "unspecified"))
      (node (ref "LED98") (pin "3") (pinfunction "VSS_3") (pintype "unspecified"))
      (node (ref "LED99") (pin "3") (pinfunction "VSS_3") (pintype "unspecified"))
      (node (ref "R2") (pin "1") (pinfunction "1_1") (pintype "unspecified"))
      (node (ref "SW1") (pin "d") (pinfunction "d_d") (pintype "unspecified"))
      (node (ref "SW2") (pin "4") (pinfunction "4_4") (pintype "unspecified"))
      (node (ref "SW2") (pin "5") (pinfunction "5_5") (pintype "unspecified"))
      (node (ref "U1") (pin "15") (pinfunction "GND_15") (pintype "unspecified"))
      (node (ref "U2") (pin "1") (pinfunction "CLKIN_1") (pintype "unspecified"))
      (node (ref "U2") (pin "11") (pinfunction "FSYNC_11") (pintype "unspecified"))
      (node (ref "U2") (pin "18") (pinfunction "GND_18") (pintype "unspecified"))
      (node (ref "U3") (pin "2") (pinfunction "GND_2") (pintype "unspecified"))
    )
    (net (code "14") (name "IR") (class "Default")
      (node (ref "U1") (pin "6") (pinfunction "D10_6") (pintype "unspecified"))
      (node (ref "U3") (pin "1") (pinfunction "OUT_1") (pintype "unspecified"))
    )
    (net (code "15") (name "LED1") (class "Default")
      (node (ref "R4") (pin "1") (pinfunction "1_1") (pintype "input"))
      (node (ref "U1") (pin "7") (pinfunction "D20_7") (pintype "unspecified"))
    )
    (net (code "16") (name "LED2") (class "Default")
      (node (ref "R5") (pin "1") (pinfunction "1_1") (pintype "input"))
      (node (ref "U1") (pin "8") (pinfunction "D21_8") (pintype "unspecified"))
    )
    (net (code "17") (name "Net-(BAT1-Pad1)") (class "Default")
      (node (ref "BAT1") (pin "1") (pinfunction "1_1") (pintype "input"))
      (node (ref "SW2") (pin "2") (pinfunction "2_2") (pintype "unspecified"))
    )
    (net (code "18") (name "Net-(LED1-DOUT)") (class "Default")
      (node (ref "LED1") (pin "2") (pinfunction "DOUT_2") (pintype "unspecified"))
      (node (ref "LED2") (pin "4") (pinfunction "DIN_4") (pintype "unspecified"))
    )
    (net (code "19") (name "Net-(LED2-DOUT)") (class "Default")
      (node (ref "LED2") (pin "2") (pinfunction "DOUT_2") (pintype "unspecified"))
      (node (ref "LED3") (pin "4") (pinfunction "DIN_4") (pintype "unspecified"))
    )
    (net (code "20") (name "Net-(LED3-DOUT)") (class "Default")
      (node (ref "LED3") (pin "2") (pinfunction "DOUT_2") (pintype "unspecified"))
      (node (ref "LED4") (pin "4") (pinfunction "DIN_4") (pintype "unspecified"))
    )
    (net (code "21") (name "Net-(LED4-DOUT)") (class "Default")
      (node (ref "LED4") (pin "2") (pinfunction "DOUT_2") (pintype "unspecified"))
      (node (ref "LED5") (pin "4") (pinfunction "DIN_4") (pintype "unspecified"))
    )
    (net (code "22") (name "Net-(LED5-DOUT)") (class "Default")
      (node (ref "LED5") (pin "2") (pinfunction "DOUT_2") (pintype "unspecified"))
      (node (ref "LED6") (pin "4") (pinfunction "DIN_4") (pintype "unspecified"))
    )
    (net (code "23") (name "Net-(LED6-DOUT)") (class "Default")
      (node (ref "LED6") (pin "2") (pinfunction "DOUT_2") (pintype "unspecified"))
      (node (ref "LED7") (pin "4") (pinfunction "DIN_4") (pintype "unspecified"))
    )
    (net (code "24") (name "Net-(LED7-DOUT)") (class "Default")
      (node (ref "LED7") (pin "2") (pinfunction "DOUT_2") (pintype "unspecified"))
      (node (ref "LED8") (pin "4") (pinfunction "DIN_4") (pintype "unspecified"))
    )
    (net (code "25") (name "Net-(LED8-DOUT)") (class "Default")
      (node (ref "LED8") (pin "2") (pinfunction "DOUT_2") (pintype "unspecified"))
      (node (ref "LED9") (pin "4") (pinfunction "DIN_4") (pintype "unspecified"))
    )
    (net (code "26") (name "Net-(LED10-DIN)") (class "Default")
      (node (ref "LED10") (pin "4") (pinfunction "DIN_4") (pintype "unspecified"))
      (node (ref "LED9") (pin "2") (pinfunction "DOUT_2") (pintype "unspecified"))
    )
    (net (code "27") (name "Net-(LED11-DOUT)") (class "Default")
      (node (ref "LED11") (pin "2") (pinfunction "DOUT_2") (pintype "unspecified"))
      (node (ref "LED12") (pin "4") (pinfunction "DIN_4") (pintype "unspecified"))
    )
    (net (code "28") (name "Net-(LED12-DOUT)") (class "Default")
      (node (ref "LED12") (pin "2") (pinfunction "DOUT_2") (pintype "unspecified"))
      (node (ref "LED13") (pin "4") (pinfunction "DIN_4") (pintype "unspecified"))
    )
    (net (code "29") (name "Net-(LED13-DOUT)") (class "Default")
      (node (ref "LED13") (pin "2") (pinfunction "DOUT_2") (pintype "unspecified"))
      (node (ref "LED14") (pin "4") (pinfunction "DIN_4") (pintype "unspecified"))
    )
    (net (code "30") (name "Net-(LED14-DOUT)") (class "Default")
      (node (ref "LED14") (pin "2") (pinfunction "DOUT_2") (pintype "unspecified"))
      (node (ref "LED15") (pin "4") (pinfunction "DIN_4") (pintype "unspecified"))
    )
    (net (code "31") (name "Net-(LED15-DOUT)") (class "Default")
      (node (ref "LED15") (pin "2") (pinfunction "DOUT_2") (pintype "unspecified"))
      (node (ref "LED16") (pin "4") (pinfunction "DIN_4") (pintype "unspecified"))
    )
    (net (code "32") (name "Net-(LED16-DOUT)") (class "Default")
      (node (ref "LED16") (pin "2") (pinfunction "DOUT_2") (pintype "unspecified"))
      (node (ref "LED17") (pin "4") (pinfunction "DIN_4") (pintype "unspecified"))
    )
    (net (code "33") (name "Net-(LED17-DOUT)") (class "Default")
      (node (ref "LED17") (pin "2") (pinfunction "DOUT_2") (pintype "unspecified"))
      (node (ref "LED18") (pin "4") (pinfunction "DIN_4") (pintype "unspecified"))
    )
    (net (code "34") (name "Net-(LED18-DOUT)") (class "Default")
      (node (ref "LED18") (pin "2") (pinfunction "DOUT_2") (pintype "unspecified"))
      (node (ref "LED19") (pin "4") (pinfunction "DIN_4") (pintype "unspecified"))
    )
    (net (code "35") (name "Net-(LED19-DOUT)") (class "Default")
      (node (ref "LED19") (pin "2") (pinfunction "DOUT_2") (pintype "unspecified"))
      (node (ref "LED20") (pin "4") (pinfunction "DIN_4") (pintype "unspecified"))
    )
    (net (code "36") (name "Net-(LED21-DOUT)") (class "Default")
      (node (ref "LED21") (pin "2") (pinfunction "DOUT_2") (pintype "unspecified"))
      (node (ref "LED22") (pin "4") (pinfunction "DIN_4") (pintype "unspecified"))
    )
    (net (code "37") (name "Net-(LED22-DOUT)") (class "Default")
      (node (ref "LED22") (pin "2") (pinfunction "DOUT_2") (pintype "unspecified"))
      (node (ref "LED23") (pin "4") (pinfunction "DIN_4") (pintype "unspecified"))
    )
    (net (code "38") (name "Net-(LED23-DOUT)") (class "Default")
      (node (ref "LED23") (pin "2") (pinfunction "DOUT_2") (pintype "unspecified"))
      (node (ref "LED24") (pin "4") (pinfunction "DIN_4") (pintype "unspecified"))
    )
    (net (code "39") (name "Net-(LED24-DOUT)") (class "Default")
      (node (ref "LED24") (pin "2") (pinfunction "DOUT_2") (pintype "unspecified"))
      (node (ref "LED25") (pin "4") (pinfunction "DIN_4") (pintype "unspecified"))
    )
    (net (code "40") (name "Net-(LED25-DOUT)") (class "Default")
      (node (ref "LED25") (pin "2") (pinfunction "DOUT_2") (pintype "unspecified"))
      (node (ref "LED26") (pin "4") (pinfunction "DIN_4") (pintype "unspecified"))
    )
    (net (code "41") (name "Net-(LED26-DOUT)") (class "Default")
      (node (ref "LED26") (pin "2") (pinfunction "DOUT_2") (pintype "unspecified"))
      (node (ref "LED27") (pin "4") (pinfunction "DIN_4") (pintype "unspecified"))
    )
    (net (code "42") (name "Net-(LED27-DOUT)") (class "Default")
      (node (ref "LED27") (pin "2") (pinfunction "DOUT_2") (pintype "unspecified"))
      (node (ref "LED28") (pin "4") (pinfunction "DIN_4") (pintype "unspecified"))
    )
    (net (code "43") (name "Net-(LED28-DOUT)") (class "Default")
      (node (ref "LED28") (pin "2") (pinfunction "DOUT_2") (pintype "unspecified"))
      (node (ref "LED29") (pin "4") (pinfunction "DIN_4") (pintype "unspecified"))
    )
    (net (code "44") (name "Net-(LED29-DOUT)") (class "Default")
      (node (ref "LED29") (pin "2") (pinfunction "DOUT_2") (pintype "unspecified"))
      (node (ref "LED30") (pin "4") (pinfunction "DIN_4") (pintype "unspecified"))
    )
    (net (code "45") (name "Net-(LED31-DOUT)") (class "Default")
      (node (ref "LED31") (pin "2") (pinfunction "DOUT_2") (pintype "unspecified"))
      (node (ref "LED32") (pin "4") (pinfunction "DIN_4") (pintype "unspecified"))
    )
    (net (code "46") (name "Net-(LED32-DOUT)") (class "Default")
      (node (ref "LED32") (pin "2") (pinfunction "DOUT_2") (pintype "unspecified"))
      (node (ref "LED33") (pin "4") (pinfunction "DIN_4") (pintype "unspecified"))
    )
    (net (code "47") (name "Net-(LED33-DOUT)") (class "Default")
      (node (ref "LED33") (pin "2") (pinfunction "DOUT_2") (pintype "unspecified"))
      (node (ref "LED34") (pin "4") (pinfunction "DIN_4") (pintype "unspecified"))
    )
    (net (code "48") (name "Net-(LED34-DOUT)") (class "Default")
      (node (ref "LED34") (pin "2") (pinfunction "DOUT_2") (pintype "unspecified"))
      (node (ref "LED35") (pin "4") (pinfunction "DIN_4") (pintype "unspecified"))
    )
    (net (code "49") (name "Net-(LED35-DOUT)") (class "Default")
      (node (ref "LED35") (pin "2") (pinfunction "DOUT_2") (pintype "unspecified"))
      (node (ref "LED36") (pin "4") (pinfunction "DIN_4") (pintype "unspecified"))
    )
    (net (code "50") (name "Net-(LED36-DOUT)") (class "Default")
      (node (ref "LED36") (pin "2") (pinfunction "DOUT_2") (pintype "unspecified"))
      (node (ref "LED37") (pin "4") (pinfunction "DIN_4") (pintype "unspecified"))
    )
    (net (code "51") (name "Net-(LED37-DOUT)") (class "Default")
      (node (ref "LED37") (pin "2") (pinfunction "DOUT_2") (pintype "unspecified"))
      (node (ref "LED38") (pin "4") (pinfunction "DIN_4") (pintype "unspecified"))
    )
    (net (code "52") (name "Net-(LED38-DOUT)") (class "Default")
      (node (ref "LED38") (pin "2") (pinfunction "DOUT_2") (pintype "unspecified"))
      (node (ref "LED39") (pin "4") (pinfunction "DIN_4") (pintype "unspecified"))
    )
    (net (code "53") (name "Net-(LED39-DOUT)") (class "Default")
      (node (ref "LED39") (pin "2") (pinfunction "DOUT_2") (pintype "unspecified"))
      (node (ref "LED40") (pin "4") (pinfunction "DIN_4") (pintype "unspecified"))
    )
    (net (code "54") (name "Net-(LED41-DOUT)") (class "Default")
      (node (ref "LED41") (pin "2") (pinfunction "DOUT_2") (pintype "unspecified"))
      (node (ref "LED42") (pin "4") (pinfunction "DIN_4") (pintype "unspecified"))
    )
    (net (code "55") (name "Net-(LED42-DOUT)") (class "Default")
      (node (ref "LED42") (pin "2") (pinfunction "DOUT_2") (pintype "unspecified"))
      (node (ref "LED43") (pin "4") (pinfunction "DIN_4") (pintype "unspecified"))
    )
    (net (code "56") (name "Net-(LED43-DOUT)") (class "Default")
      (node (ref "LED43") (pin "2") (pinfunction "DOUT_2") (pintype "unspecified"))
      (node (ref "LED44") (pin "4") (pinfunction "DIN_4") (pintype "unspecified"))
    )
    (net (code "57") (name "Net-(LED44-DOUT)") (class "Default")
      (node (ref "LED44") (pin "2") (pinfunction "DOUT_2") (pintype "unspecified"))
      (node (ref "LED45") (pin "4") (pinfunction "DIN_4") (pintype "unspecified"))
    )
    (net (code "58") (name "Net-(LED45-DOUT)") (class "Default")
      (node (ref "LED45") (pin "2") (pinfunction "DOUT_2") (pintype "unspecified"))
      (node (ref "LED46") (pin "4") (pinfunction "DIN_4") (pintype "unspecified"))
    )
    (net (code "59") (name "Net-(LED46-DOUT)") (class "Default")
      (node (ref "LED46") (pin "2") (pinfunction "DOUT_2") (pintype "unspecified"))
      (node (ref "LED47") (pin "4") (pinfunction "DIN_4") (pintype "unspecified"))
    )
    (net (code "60") (name "Net-(LED47-DOUT)") (class "Default")
      (node (ref "LED47") (pin "2") (pinfunction "DOUT_2") (pintype "unspecified"))
      (node (ref "LED48") (pin "4") (pinfunction "DIN_4") (pintype "unspecified"))
    )
    (net (code "61") (name "Net-(LED48-DOUT)") (class "Default")
      (node (ref "LED48") (pin "2") (pinfunction "DOUT_2") (pintype "unspecified"))
      (node (ref "LED49") (pin "4") (pinfunction "DIN_4") (pintype "unspecified"))
    )
    (net (code "62") (name "Net-(LED49-DOUT)") (class "Default")
      (node (ref "LED49") (pin "2") (pinfunction "DOUT_2") (pintype "unspecified"))
      (node (ref "LED50") (pin "4") (pinfunction "DIN_4") (pintype "unspecified"))
    )
    (net (code "63") (name "Net-(LED51-DOUT)") (class "Default")
      (node (ref "LED51") (pin "2") (pinfunction "DOUT_2") (pintype "unspecified"))
      (node (ref "LED52") (pin "4") (pinfunction "DIN_4") (pintype "unspecified"))
    )
    (net (code "64") (name "Net-(LED52-DOUT)") (class "Default")
      (node (ref "LED52") (pin "2") (pinfunction "DOUT_2") (pintype "unspecified"))
      (node (ref "LED53") (pin "4") (pinfunction "DIN_4") (pintype "unspecified"))
    )
    (net (code "65") (name "Net-(LED53-DOUT)") (class "Default")
      (node (ref "LED53") (pin "2") (pinfunction "DOUT_2") (pintype "unspecified"))
      (node (ref "LED54") (pin "4") (pinfunction "DIN_4") (pintype "unspecified"))
    )
    (net (code "66") (name "Net-(LED54-DOUT)") (class "Default")
      (node (ref "LED54") (pin "2") (pinfunction "DOUT_2") (pintype "unspecified"))
      (node (ref "LED55") (pin "4") (pinfunction "DIN_4") (pintype "unspecified"))
    )
    (net (code "67") (name "Net-(LED55-DOUT)") (class "Default")
      (node (ref "LED55") (pin "2") (pinfunction "DOUT_2") (pintype "unspecified"))
      (node (ref "LED56") (pin "4") (pinfunction "DIN_4") (pintype "unspecified"))
    )
    (net (code "68") (name "Net-(LED56-DOUT)") (class "Default")
      (node (ref "LED56") (pin "2") (pinfunction "DOUT_2") (pintype "unspecified"))
      (node (ref "LED57") (pin "4") (pinfunction "DIN_4") (pintype "unspecified"))
    )
    (net (code "69") (name "Net-(LED57-DOUT)") (class "Default")
      (node (ref "LED57") (pin "2") (pinfunction "DOUT_2") (pintype "unspecified"))
      (node (ref "LED58") (pin "4") (pinfunction "DIN_4") (pintype "unspecified"))
    )
    (net (code "70") (name "Net-(LED58-DOUT)") (class "Default")
      (node (ref "LED58") (pin "2") (pinfunction "DOUT_2") (pintype "unspecified"))
      (node (ref "LED59") (pin "4") (pinfunction "DIN_4") (pintype "unspecified"))
    )
    (net (code "71") (name "Net-(LED59-DOUT)") (class "Default")
      (node (ref "LED59") (pin "2") (pinfunction "DOUT_2") (pintype "unspecified"))
      (node (ref "LED60") (pin "4") (pinfunction "DIN_4") (pintype "unspecified"))
    )
    (net (code "72") (name "Net-(LED61-DOUT)") (class "Default")
      (node (ref "LED61") (pin "2") (pinfunction "DOUT_2") (pintype "unspecified"))
      (node (ref "LED62") (pin "4") (pinfunction "DIN_4") (pintype "unspecified"))
    )
    (net (code "73") (name "Net-(LED62-DOUT)") (class "Default")
      (node (ref "LED62") (pin "2") (pinfunction "DOUT_2") (pintype "unspecified"))
      (node (ref "LED63") (pin "4") (pinfunction "DIN_4") (pintype "unspecified"))
    )
    (net (code "74") (name "Net-(LED63-DOUT)") (class "Default")
      (node (ref "LED63") (pin "2") (pinfunction "DOUT_2") (pintype "unspecified"))
      (node (ref "LED64") (pin "4") (pinfunction "DIN_4") (pintype "unspecified"))
    )
    (net (code "75") (name "Net-(LED64-DOUT)") (class "Default")
      (node (ref "LED64") (pin "2") (pinfunction "DOUT_2") (pintype "unspecified"))
      (node (ref "LED65") (pin "4") (pinfunction "DIN_4") (pintype "unspecified"))
    )
    (net (code "76") (name "Net-(LED65-DOUT)") (class "Default")
      (node (ref "LED65") (pin "2") (pinfunction "DOUT_2") (pintype "unspecified"))
      (node (ref "LED66") (pin "4") (pinfunction "DIN_4") (pintype "unspecified"))
    )
    (net (code "77") (name "Net-(LED66-DOUT)") (class "Default")
      (node (ref "LED66") (pin "2") (pinfunction "DOUT_2") (pintype "unspecified"))
      (node (ref "LED67") (pin "4") (pinfunction "DIN_4") (pintype "unspecified"))
    )
    (net (code "78") (name "Net-(LED67-DOUT)") (class "Default")
      (node (ref "LED67") (pin "2") (pinfunction "DOUT_2") (pintype "unspecified"))
      (node (ref "LED68") (pin "4") (pinfunction "DIN_4") (pintype "unspecified"))
    )
    (net (code "79") (name "Net-(LED68-DOUT)") (class "Default")
      (node (ref "LED68") (pin "2") (pinfunction "DOUT_2") (pintype "unspecified"))
      (node (ref "LED69") (pin "4") (pinfunction "DIN_4") (pintype "unspecified"))
    )
    (net (code "80") (name "Net-(LED69-DOUT)") (class "Default")
      (node (ref "LED69") (pin "2") (pinfunction "DOUT_2") (pintype "unspecified"))
      (node (ref "LED70") (pin "4") (pinfunction "DIN_4") (pintype "unspecified"))
    )
    (net (code "81") (name "Net-(LED71-DOUT)") (class "Default")
      (node (ref "LED71") (pin "2") (pinfunction "DOUT_2") (pintype "unspecified"))
      (node (ref "LED72") (pin "4") (pinfunction "DIN_4") (pintype "unspecified"))
    )
    (net (code "82") (name "Net-(LED72-DOUT)") (class "Default")
      (node (ref "LED72") (pin "2") (pinfunction "DOUT_2") (pintype "unspecified"))
      (node (ref "LED73") (pin "4") (pinfunction "DIN_4") (pintype "unspecified"))
    )
    (net (code "83") (name "Net-(LED73-DOUT)") (class "Default")
      (node (ref "LED73") (pin "2") (pinfunction "DOUT_2") (pintype "unspecified"))
      (node (ref "LED74") (pin "4") (pinfunction "DIN_4") (pintype "unspecified"))
    )
    (net (code "84") (name "Net-(LED74-DOUT)") (class "Default")
      (node (ref "LED74") (pin "2") (pinfunction "DOUT_2") (pintype "unspecified"))
      (node (ref "LED75") (pin "4") (pinfunction "DIN_4") (pintype "unspecified"))
    )
    (net (code "85") (name "Net-(LED75-DOUT)") (class "Default")
      (node (ref "LED75") (pin "2") (pinfunction "DOUT_2") (pintype "unspecified"))
      (node (ref "LED76") (pin "4") (pinfunction "DIN_4") (pintype "unspecified"))
    )
    (net (code "86") (name "Net-(LED76-DOUT)") (class "Default")
      (node (ref "LED76") (pin "2") (pinfunction "DOUT_2") (pintype "unspecified"))
      (node (ref "LED77") (pin "4") (pinfunction "DIN_4") (pintype "unspecified"))
    )
    (net (code "87") (name "Net-(LED77-DOUT)") (class "Default")
      (node (ref "LED77") (pin "2") (pinfunction "DOUT_2") (pintype "unspecified"))
      (node (ref "LED78") (pin "4") (pinfunction "DIN_4") (pintype "unspecified"))
    )
    (net (code "88") (name "Net-(LED78-DOUT)") (class "Default")
      (node (ref "LED78") (pin "2") (pinfunction "DOUT_2") (pintype "unspecified"))
      (node (ref "LED79") (pin "4") (pinfunction "DIN_4") (pintype "unspecified"))
    )
    (net (code "89") (name "Net-(LED79-DOUT)") (class "Default")
      (node (ref "LED79") (pin "2") (pinfunction "DOUT_2") (pintype "unspecified"))
      (node (ref "LED80") (pin "4") (pinfunction "DIN_4") (pintype "unspecified"))
    )
    (net (code "90") (name "Net-(LED81-DOUT)") (class "Default")
      (node (ref "LED81") (pin "2") (pinfunction "DOUT_2") (pintype "unspecified"))
      (node (ref "LED82") (pin "4") (pinfunction "DIN_4") (pintype "unspecified"))
    )
    (net (code "91") (name "Net-(LED82-DOUT)") (class "Default")
      (node (ref "LED82") (pin "2") (pinfunction "DOUT_2") (pintype "unspecified"))
      (node (ref "LED83") (pin "4") (pinfunction "DIN_4") (pintype "unspecified"))
    )
    (net (code "92") (name "Net-(LED83-DOUT)") (class "Default")
      (node (ref "LED83") (pin "2") (pinfunction "DOUT_2") (pintype "unspecified"))
      (node (ref "LED84") (pin "4") (pinfunction "DIN_4") (pintype "unspecified"))
    )
    (net (code "93") (name "Net-(LED84-DOUT)") (class "Default")
      (node (ref "LED84") (pin "2") (pinfunction "DOUT_2") (pintype "unspecified"))
      (node (ref "LED85") (pin "4") (pinfunction "DIN_4") (pintype "unspecified"))
    )
    (net (code "94") (name "Net-(LED85-DOUT)") (class "Default")
      (node (ref "LED85") (pin "2") (pinfunction "DOUT_2") (pintype "unspecified"))
      (node (ref "LED86") (pin "4") (pinfunction "DIN_4") (pintype "unspecified"))
    )
    (net (code "95") (name "Net-(LED86-DOUT)") (class "Default")
      (node (ref "LED86") (pin "2") (pinfunction "DOUT_2") (pintype "unspecified"))
      (node (ref "LED87") (pin "4") (pinfunction "DIN_4") (pintype "unspecified"))
    )
    (net (code "96") (name "Net-(LED87-DOUT)") (class "Default")
      (node (ref "LED87") (pin "2") (pinfunction "DOUT_2") (pintype "unspecified"))
      (node (ref "LED88") (pin "4") (pinfunction "DIN_4") (pintype "unspecified"))
    )
    (net (code "97") (name "Net-(LED88-DOUT)") (class "Default")
      (node (ref "LED88") (pin "2") (pinfunction "DOUT_2") (pintype "unspecified"))
      (node (ref "LED89") (pin "4") (pinfunction "DIN_4") (pintype "unspecified"))
    )
    (net (code "98") (name "Net-(LED89-DOUT)") (class "Default")
      (node (ref "LED89") (pin "2") (pinfunction "DOUT_2") (pintype "unspecified"))
      (node (ref "LED90") (pin "4") (pinfunction "DIN_4") (pintype "unspecified"))
    )
    (net (code "99") (name "Net-(LED91-DOUT)") (class "Default")
      (node (ref "LED91") (pin "2") (pinfunction "DOUT_2") (pintype "unspecified"))
      (node (ref "LED92") (pin "4") (pinfunction "DIN_4") (pintype "unspecified"))
    )
    (net (code "100") (name "Net-(LED92-DOUT)") (class "Default")
      (node (ref "LED92") (pin "2") (pinfunction "DOUT_2") (pintype "unspecified"))
      (node (ref "LED93") (pin "4") (pinfunction "DIN_4") (pintype "unspecified"))
    )
    (net (code "101") (name "Net-(LED93-DOUT)") (class "Default")
      (node (ref "LED93") (pin "2") (pinfunction "DOUT_2") (pintype "unspecified"))
      (node (ref "LED94") (pin "4") (pinfunction "DIN_4") (pintype "unspecified"))
    )
    (net (code "102") (name "Net-(LED94-DOUT)") (class "Default")
      (node (ref "LED94") (pin "2") (pinfunction "DOUT_2") (pintype "unspecified"))
      (node (ref "LED95") (pin "4") (pinfunction "DIN_4") (pintype "unspecified"))
    )
    (net (code "103") (name "Net-(LED95-DOUT)") (class "Default")
      (node (ref "LED95") (pin "2") (pinfunction "DOUT_2") (pintype "unspecified"))
      (node (ref "LED96") (pin "4") (pinfunction "DIN_4") (pintype "unspecified"))
    )
    (net (code "104") (name "Net-(LED96-DOUT)") (class "Default")
      (node (ref "LED96") (pin "2") (pinfunction "DOUT_2") (pintype "unspecified"))
      (node (ref "LED97") (pin "4") (pinfunction "DIN_4") (pintype "unspecified"))
    )
    (net (code "105") (name "Net-(LED97-DOUT)") (class "Default")
      (node (ref "LED97") (pin "2") (pinfunction "DOUT_2") (pintype "unspecified"))
      (node (ref "LED98") (pin "4") (pinfunction "DIN_4") (pintype "unspecified"))
    )
    (net (code "106") (name "Net-(LED98-DOUT)") (class "Default")
      (node (ref "LED98") (pin "2") (pinfunction "DOUT_2") (pintype "unspecified"))
      (node (ref "LED99") (pin "4") (pinfunction "DIN_4") (pintype "unspecified"))
    )
    (net (code "107") (name "Net-(LED100-DIN)") (class "Default")
      (node (ref "LED100") (pin "4") (pinfunction "DIN_4") (pintype "unspecified"))
      (node (ref "LED99") (pin "2") (pinfunction "DOUT_2") (pintype "unspecified"))
    )
    (net (code "108") (name "Net-(LED101-A)") (class "Default")
      (node (ref "LED101") (pin "2") (pinfunction "A_2") (pintype "unspecified"))
      (node (ref "R4") (pin "2") (pinfunction "2_2") (pintype "input"))
    )
    (net (code "109") (name "Net-(LED102-A)") (class "Default")
      (node (ref "LED102") (pin "2") (pinfunction "A_2") (pintype "unspecified"))
      (node (ref "R5") (pin "2") (pinfunction "2_2") (pintype "input"))
    )
    (net (code "110") (name "Net-(U2-AD0)") (class "Default")
      (node (ref "R2") (pin "2") (pinfunction "2_2") (pintype "unspecified"))
      (node (ref "U2") (pin "9") (pinfunction "AD0_9") (pintype "unspecified"))
    )
    (net (code "111") (name "Net-(U2-CPOUT)") (class "Default")
      (node (ref "C3") (pin "2") (pinfunction "2_2") (pintype "unspecified"))
      (node (ref "U2") (pin "20") (pinfunction "CPOUT_20") (pintype "unspecified"))
    )
    (net (code "112") (name "Net-(U2-REGOUT)") (class "Default")
      (node (ref "C2") (pin "2") (pinfunction "2_2") (pintype "unspecified"))
      (node (ref "U2") (pin "10") (pinfunction "REGOUT_10") (pintype "unspecified"))
    )
    (net (code "113") (name "SCL") (class "Default")
      (node (ref "R3") (pin "1") (pinfunction "1_1") (pintype "unspecified"))
      (node (ref "U1") (pin "5") (pinfunction "D9-SDL_5") (pintype "unspecified"))
      (node (ref "U2") (pin "23") (pinfunction "SCL_23") (pintype "unspecified"))
    )
    (net (code "114") (name "SDA") (class "Default")
      (node (ref "R1") (pin "1") (pinfunction "1_1") (pintype "unspecified"))
      (node (ref "U1") (pin "4") (pinfunction "D8-SDA_4") (pintype "unspecified"))
      (node (ref "U2") (pin "24") (pinfunction "SDA_24") (pintype "unspecified"))
    )
    (net (code "115") (name "SWITCH") (class "Default")
      (node (ref "SW1") (pin "a") (pinfunction "a_a") (pintype "unspecified"))
      (node (ref "U1") (pin "3") (pinfunction "D7_3") (pintype "unspecified"))
    )
    (net (code "116") (name "unconnected-(LED100-DOUT-Pad2)") (class "Default")
      (node (ref "LED100") (pin "2") (pinfunction "DOUT_2") (pintype "unspecified+no_connect"))
    )
    (net (code "117") (name "unconnected-(SW1-Padb)") (class "Default")
      (node (ref "SW1") (pin "b") (pinfunction "b_b") (pintype "unspecified"))
    )
    (net (code "118") (name "unconnected-(SW1-Padh)") (class "Default")
      (node (ref "SW1") (pin "h") (pinfunction "h_h") (pintype "unspecified"))
    )
    (net (code "119") (name "unconnected-(SW2-Pad3)") (class "Default")
      (node (ref "SW2") (pin "3") (pinfunction "3_3") (pintype "unspecified"))
    )
    (net (code "120") (name "unconnected-(U1-D0-A0-Pad9)") (class "Default")
      (node (ref "U1") (pin "9") (pinfunction "D0-A0_9") (pintype "unspecified"))
    )
    (net (code "121") (name "unconnected-(U1-D1-A1-Pad10)") (class "Default")
      (node (ref "U1") (pin "10") (pinfunction "D1-A1_10") (pintype "unspecified"))
    )
    (net (code "122") (name "unconnected-(U1-D2-A2-Pad11)") (class "Default")
      (node (ref "U1") (pin "11") (pinfunction "D2-A2_11") (pintype "unspecified"))
    )
    (net (code "123") (name "unconnected-(U1-D3-A3-Pad12)") (class "Default")
      (node (ref "U1") (pin "12") (pinfunction "D3-A3_12") (pintype "unspecified"))
    )
    (net (code "124") (name "unconnected-(U1-D4-A4-Pad13)") (class "Default")
      (node (ref "U1") (pin "13") (pinfunction "D4-A4_13") (pintype "unspecified"))
    )
    (net (code "125") (name "unconnected-(U1-D5-A5-Pad1)") (class "Default")
      (node (ref "U1") (pin "1") (pinfunction "D5-A5_1") (pintype "unspecified"))
    )
    (net (code "126") (name "unconnected-(U2-AUX_CL-Pad7)") (class "Default")
      (node (ref "U2") (pin "7") (pinfunction "AUX_CL_7") (pintype "unspecified"))
    )
    (net (code "127") (name "unconnected-(U2-AUX_DA-Pad6)") (class "Default")
      (node (ref "U2") (pin "6") (pinfunction "AUX_DA_6") (pintype "unspecified"))
    )
    (net (code "128") (name "unconnected-(U2-EP-Pad25)") (class "Default")
      (node (ref "U2") (pin "25") (pinfunction "EP_25") (pintype "unspecified+no_connect"))
    )
    (net (code "129") (name "unconnected-(U2-INT-Pad12)") (class "Default")
      (node (ref "U2") (pin "12") (pinfunction "INT_12") (pintype "unspecified"))
    )
    (net (code "130") (name "unconnected-(U2-NC-Pad2)") (class "Default")
      (node (ref "U2") (pin "2") (pinfunction "NC_2") (pintype "unspecified"))
    )
    (net (code "131") (name "unconnected-(U2-NC-Pad3)") (class "Default")
      (node (ref "U2") (pin "3") (pinfunction "NC_3") (pintype "unspecified"))
    )
    (net (code "132") (name "unconnected-(U2-NC-Pad4)") (class "Default")
      (node (ref "U2") (pin "4") (pinfunction "NC_4") (pintype "unspecified"))
    )
    (net (code "133") (name "unconnected-(U2-NC-Pad5)") (class "Default")
      (node (ref "U2") (pin "5") (pinfunction "NC_5") (pintype "unspecified"))
    )
    (net (code "134") (name "unconnected-(U2-NC-Pad14)") (class "Default")
      (node (ref "U2") (pin "14") (pinfunction "NC_14") (pintype "unspecified"))
    )
    (net (code "135") (name "unconnected-(U2-NC-Pad15)") (class "Default")
      (node (ref "U2") (pin "15") (pinfunction "NC_15") (pintype "unspecified"))
    )
    (net (code "136") (name "unconnected-(U2-NC-Pad16)") (class "Default")
      (node (ref "U2") (pin "16") (pinfunction "NC_16") (pintype "unspecified"))
    )
    (net (code "137") (name "unconnected-(U2-NC-Pad17)") (class "Default")
      (node (ref "U2") (pin "17") (pinfunction "NC_17") (pintype "unspecified"))
    )
    (net (code "138") (name "unconnected-(U2-RESV-Pad19)") (class "Default")
      (node (ref "U2") (pin "19") (pinfunction "RESV_19") (pintype "unspecified"))
    )
    (net (code "139") (name "unconnected-(U2-RESV-Pad21)") (class "Default")
      (node (ref "U2") (pin "21") (pinfunction "RESV_21") (pintype "unspecified"))
    )
    (net (code "140") (name "unconnected-(U2-RESV-Pad22)") (class "Default")
      (node (ref "U2") (pin "22") (pinfunction "RESV_22") (pintype "unspecified"))
    )
  )
)
